# Tractive_System_Board_Rev8.net
KiCad netlist of a schematic drawn in EAGLE
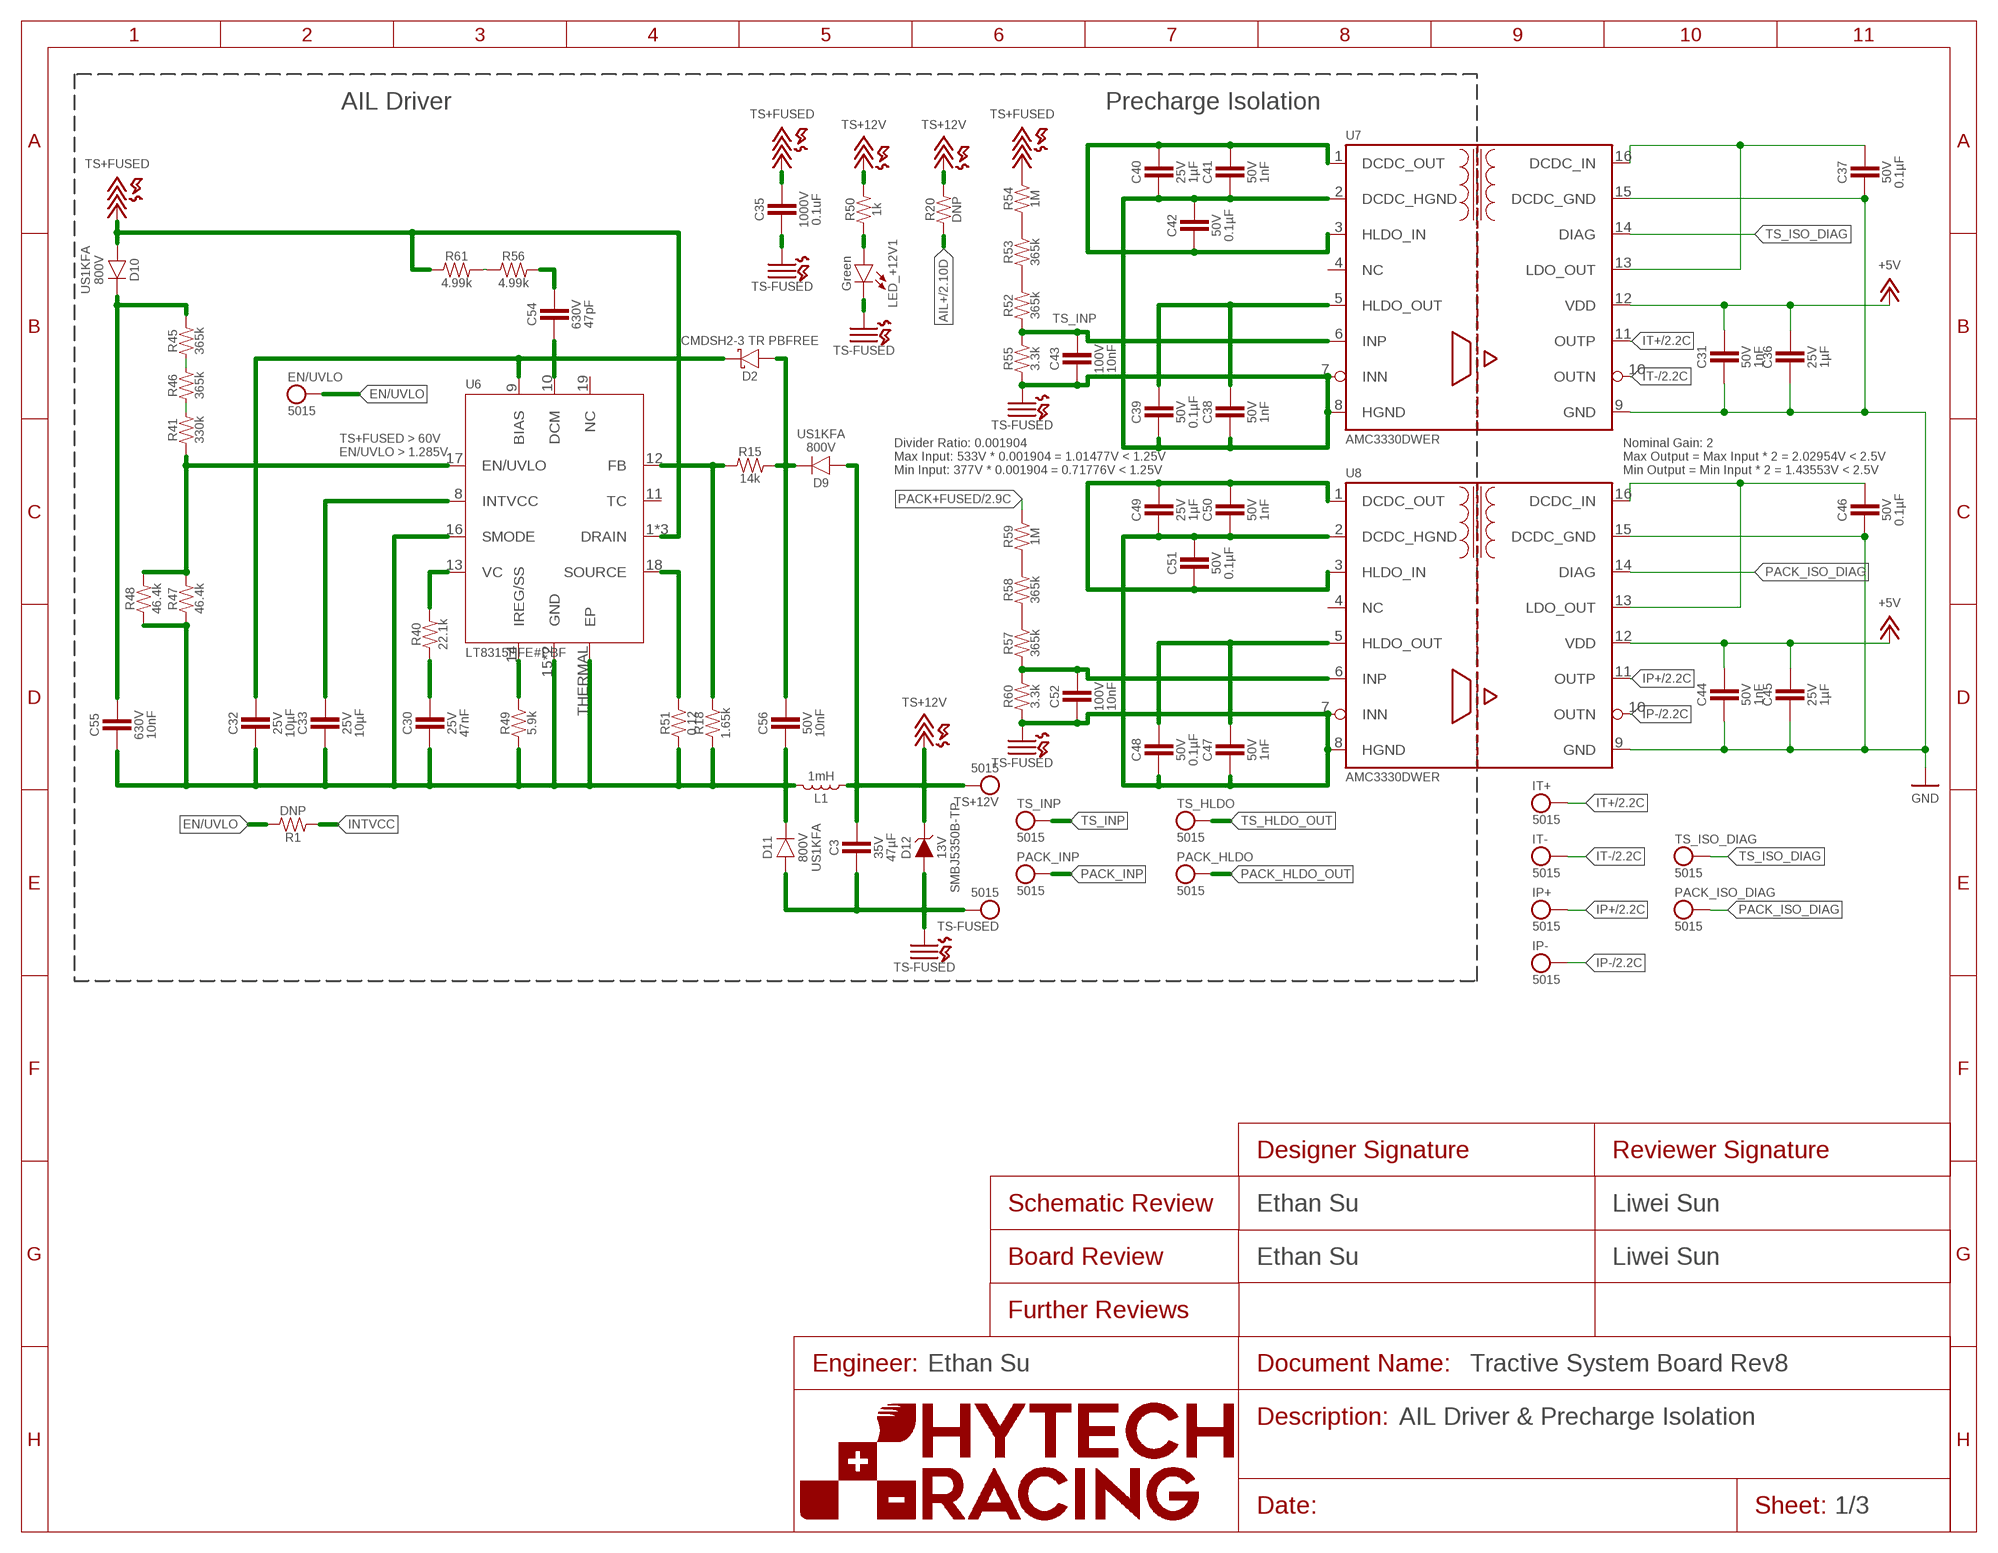
[diagram p0: schematic, sheet 1]
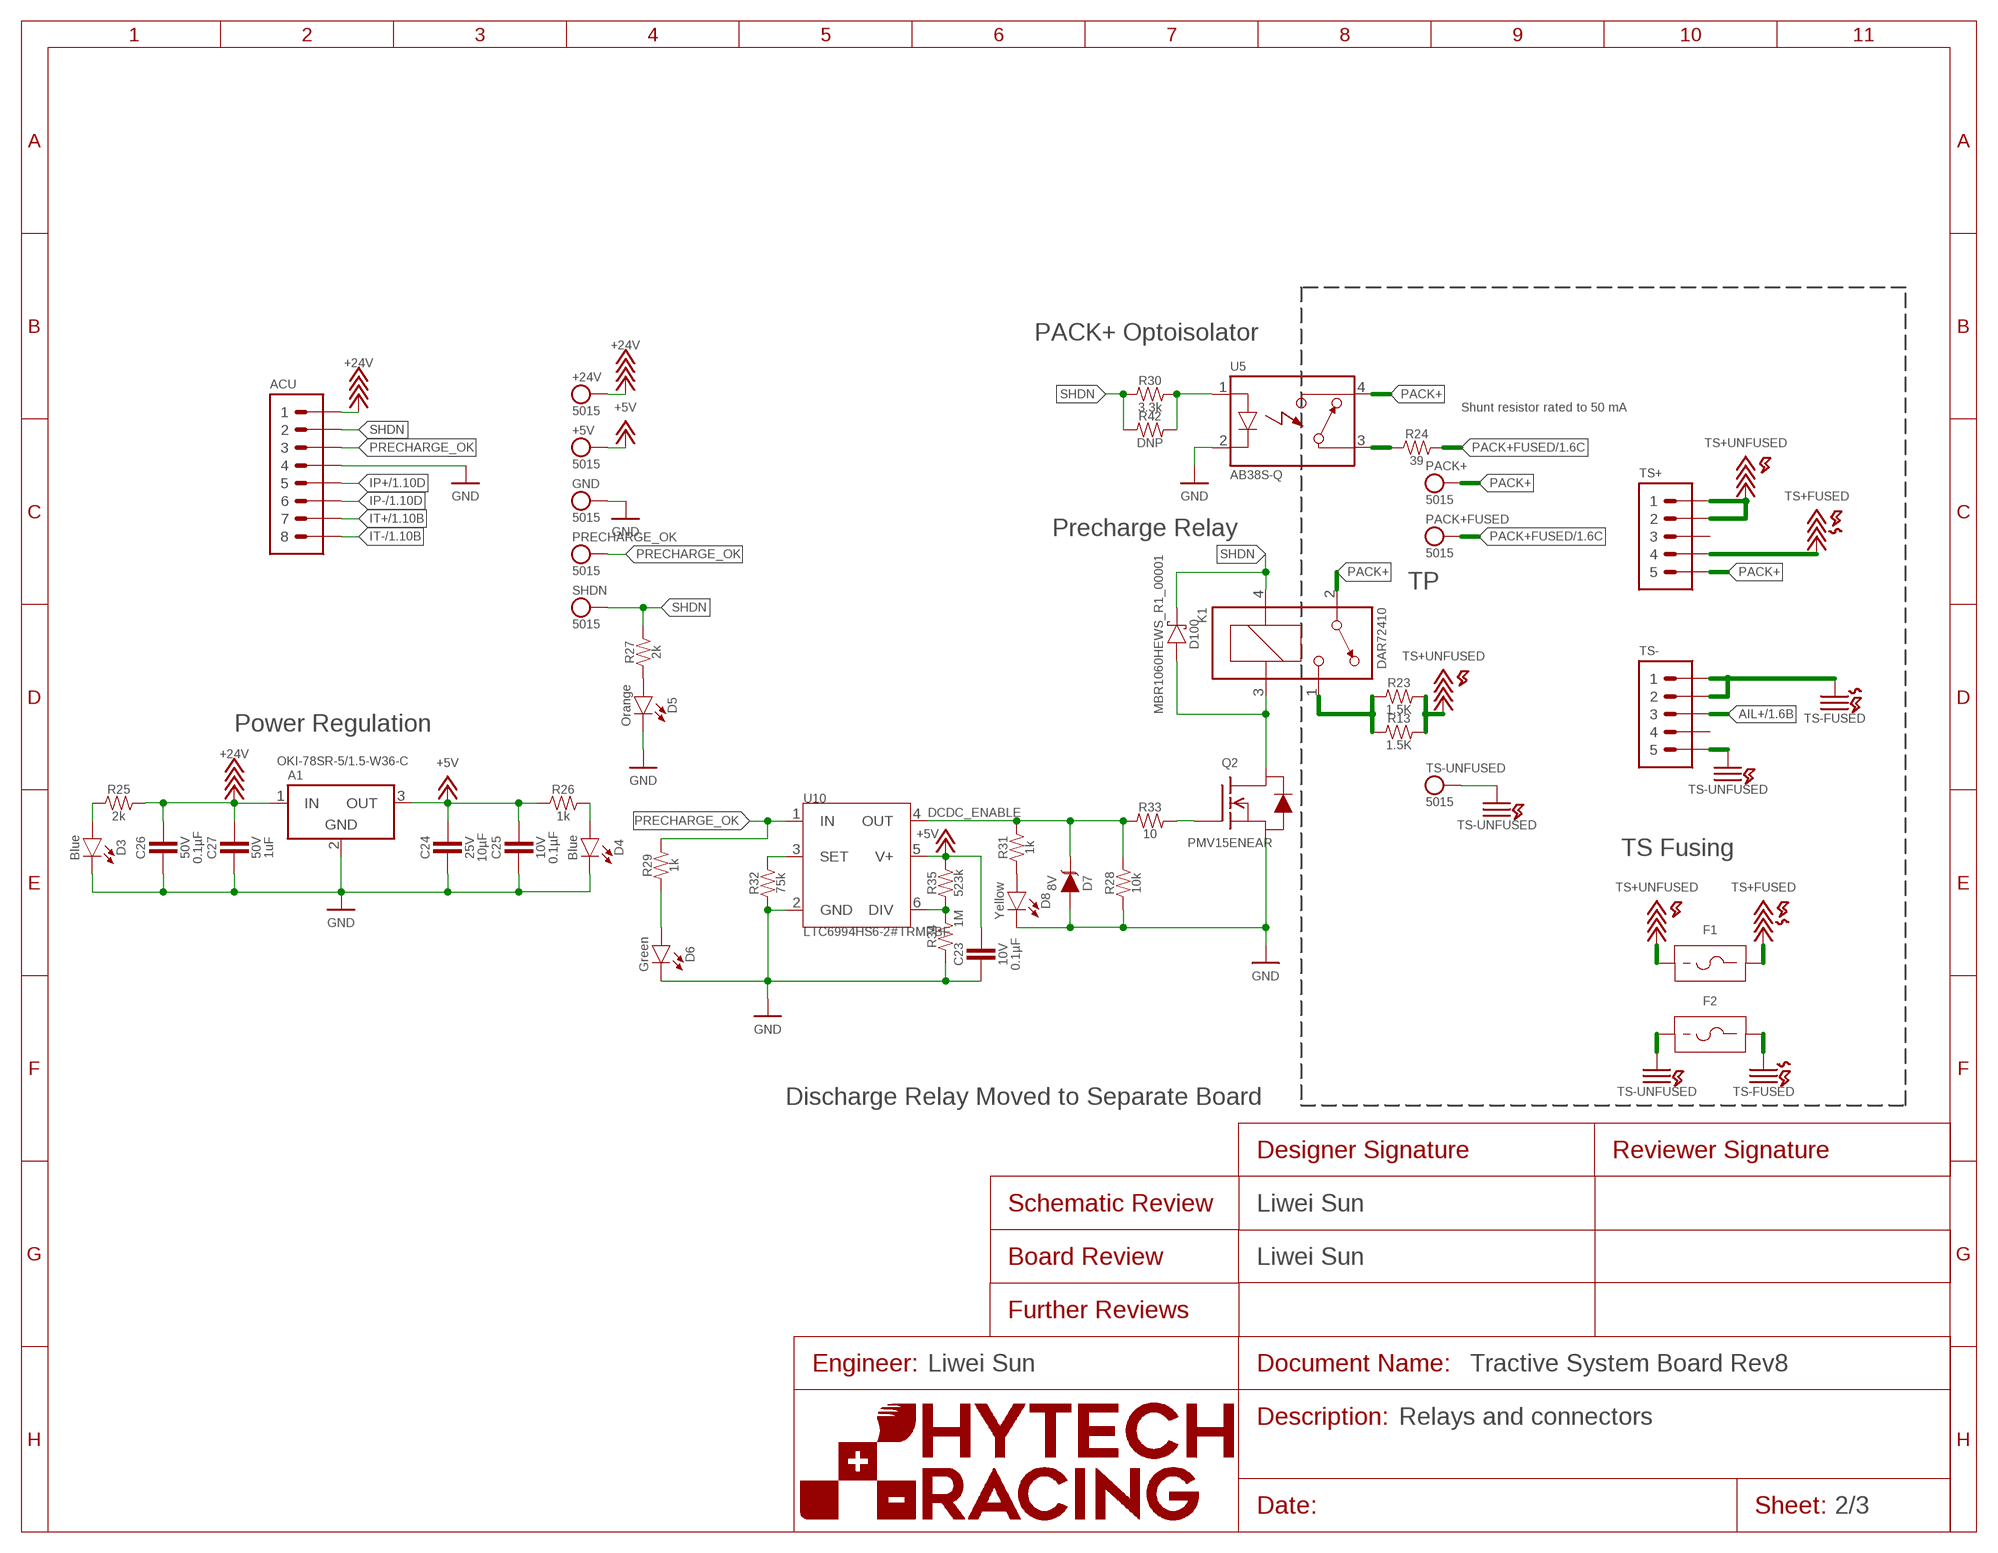
[diagram p1: schematic, sheet 2]
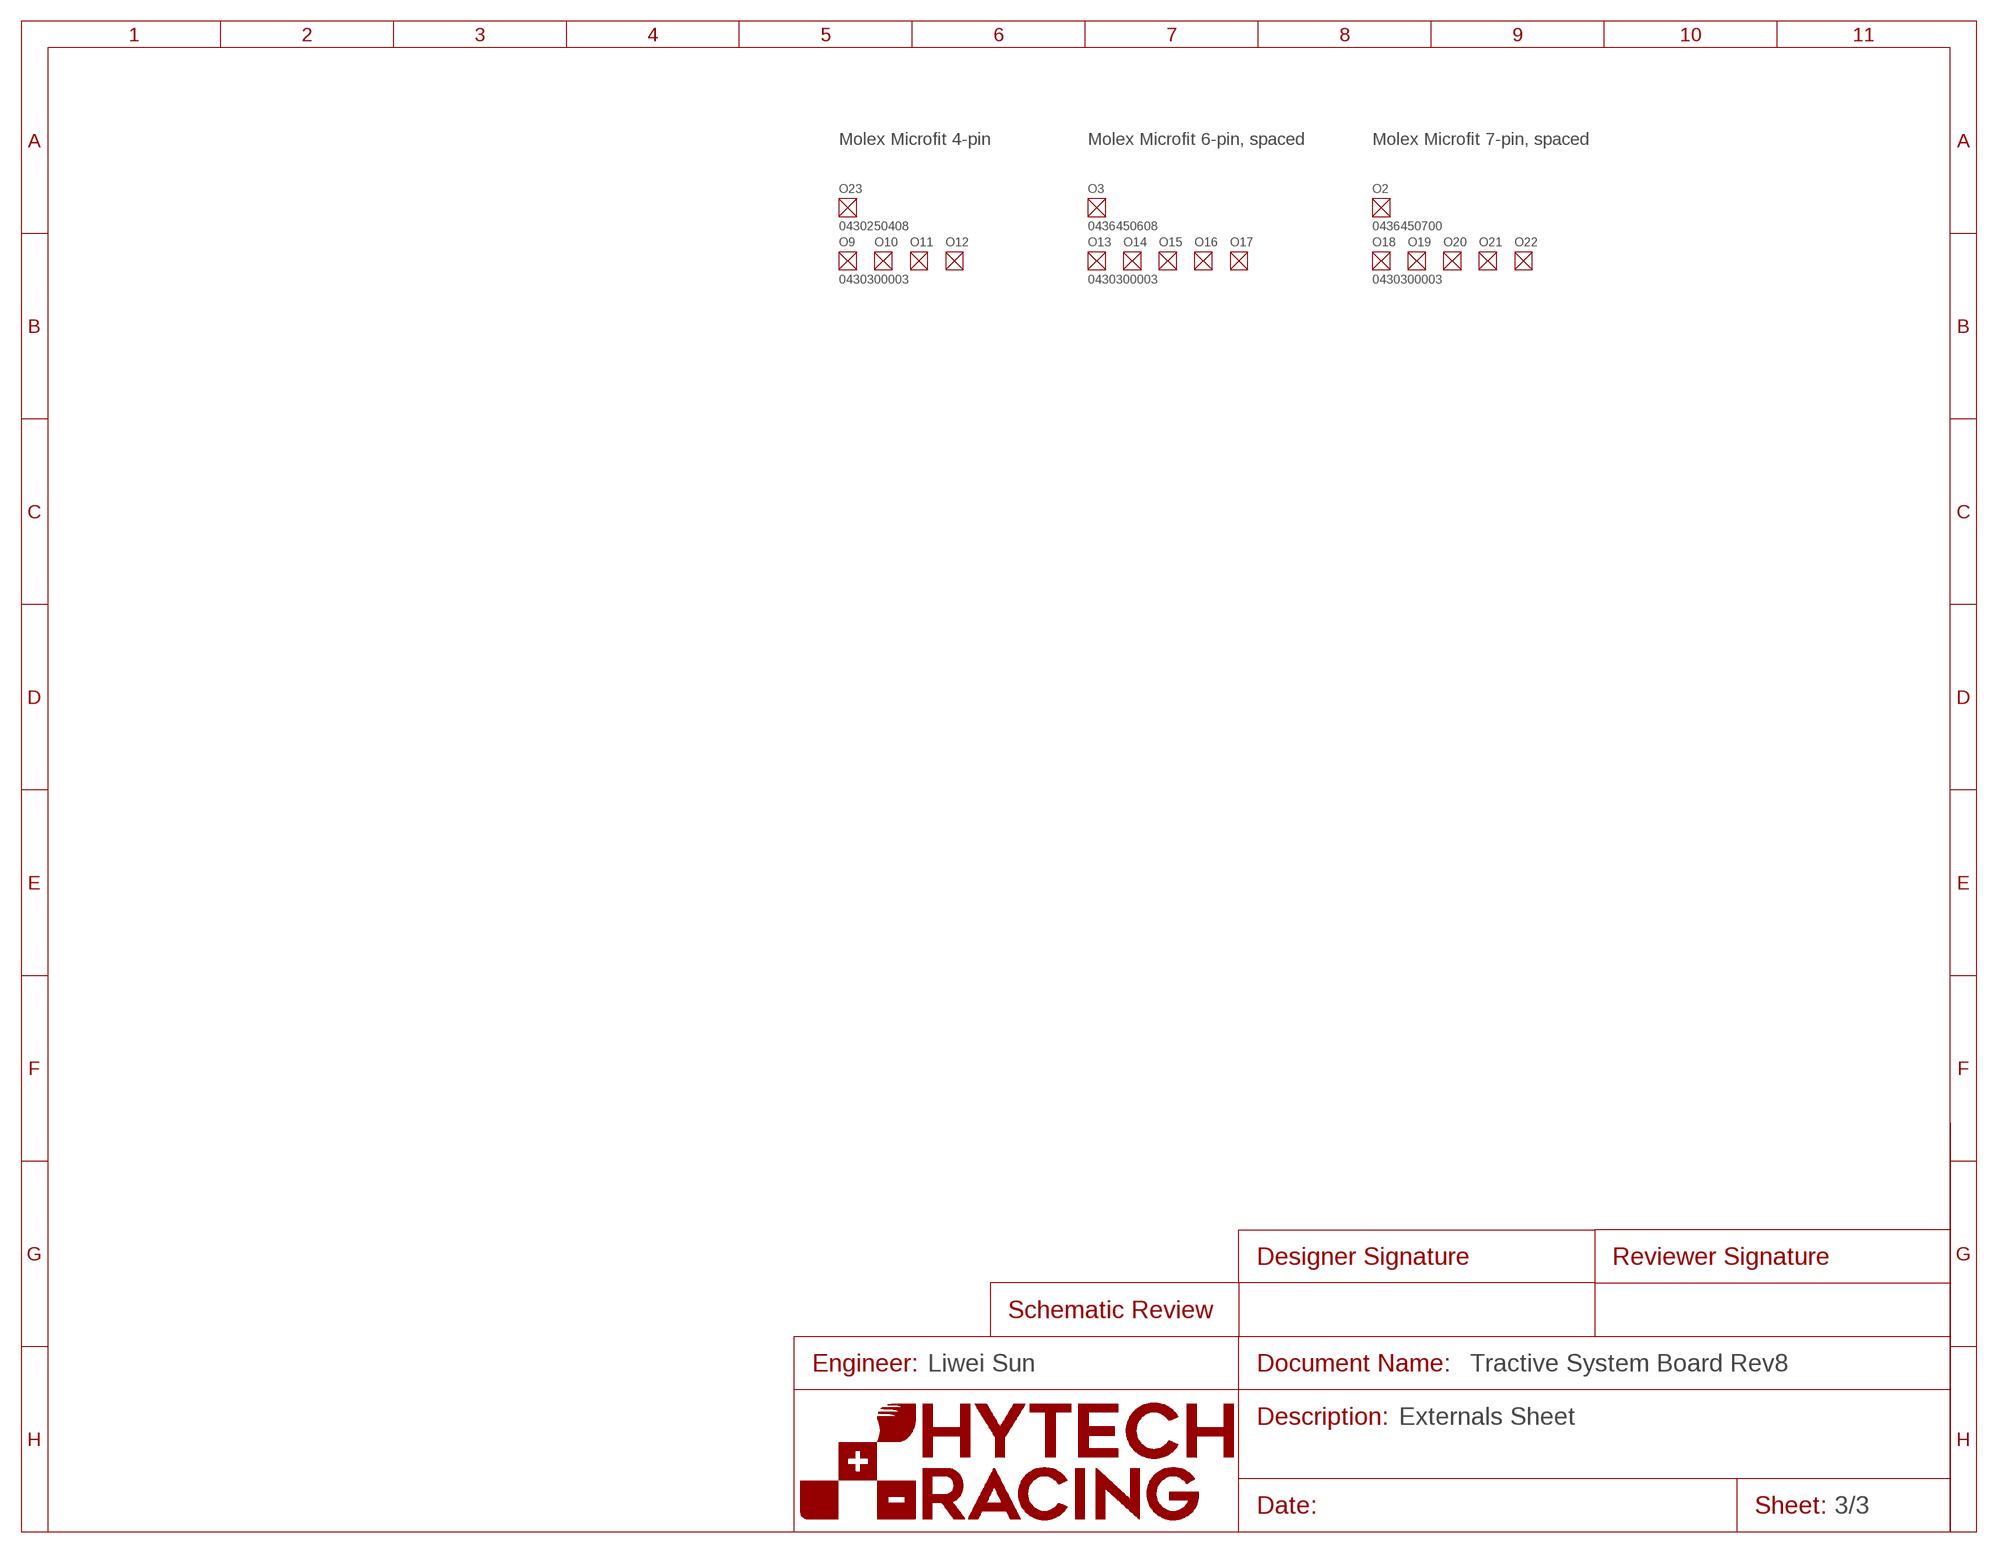
[diagram p2: schematic, sheet 3]

(export (version "E")
  (design (tool "Eeschema 10.0.6"))
  (components
    (comp (ref "C3")
      (value "CAPACITOR_2220_35V_47UF")
      (footprint "eagle-import:2220-CAP")
      (fields
        (field (name "CAPACITANCE") "47µF")
        (field (name "MANUFACTURER") "TDK Corporation")
        (field (name "MPN") "CGA9N1X7R1V476M230KC")
        (field (name "TOLERANCE") "20%")
        (field (name "VOLTAGE") "35V")
      )
      (libsource (lib "eagle-import") (part "CAPACITOR_?_222035V_47UF"))
    )
    (comp (ref "C30")
      (value "CAPACITOR_0603_25V_47NF")
      (footprint "eagle-import:0603-CAP")
      (fields
        (field (name "CAPACITANCE") "47nF")
        (field (name "MANUFACTURER") "Kyocera AVX")
        (field (name "MPN") "06033C473K4Z2A")
        (field (name "TOLERANCE") "10%")
        (field (name "VOLTAGE") "25V")
      )
      (libsource (lib "eagle-import") (part "CAPACITOR_?_060325V_47NF"))
    )
    (comp (ref "C31")
      (value "CAPACITOR_1206_50V_1NF")
      (footprint "eagle-import:1206-CAP")
      (fields
        (field (name "CAPACITANCE") "1nF")
        (field (name "MANUFACTURER") "KYOCERA AVX")
        (field (name "MPN") "KGM31BR71H102KT")
        (field (name "TOLERANCE") "10%")
        (field (name "VOLTAGE") "50V")
      )
      (libsource (lib "eagle-import") (part "CAPACITOR_?_120650V_1NF"))
    )
    (comp (ref "C32")
      (value "CAPACITOR_0603_25V_10UF")
      (footprint "eagle-import:0603-CAP")
      (fields
        (field (name "CAPACITANCE") "10µF")
        (field (name "MANUFACTURER") "Murata Electronics")
        (field (name "MPN") "GRM188R61E106MA73D")
        (field (name "TOLERANCE") "20%")
        (field (name "VOLTAGE") "25V")
      )
      (libsource (lib "eagle-import") (part "CAPACITOR_?_060325V_10UF"))
    )
    (comp (ref "C33")
      (value "CAPACITOR_0603_25V_10UF")
      (footprint "eagle-import:0603-CAP")
      (fields
        (field (name "CAPACITANCE") "10µF")
        (field (name "MANUFACTURER") "Murata Electronics")
        (field (name "MPN") "GRM188R61E106MA73D")
        (field (name "TOLERANCE") "20%")
        (field (name "VOLTAGE") "25V")
      )
      (libsource (lib "eagle-import") (part "CAPACITOR_?_060325V_10UF"))
    )
    (comp (ref "C35")
      (value "CAPACITOR_1812_1000V_0.1UF")
      (footprint "eagle-import:1812-CAP")
      (fields
        (field (name "CAPACITANCE") "0.1uF")
        (field (name "MANUFACTURER") "KEMET")
        (field (name "MPN") "C1812W104KDRAC7800")
        (field (name "TOLERANCE") "10%")
        (field (name "VOLTAGE") "1000V")
      )
      (libsource (lib "eagle-import") (part "CAPACITOR_?_18121000V_0.1UF"))
    )
    (comp (ref "C36")
      (value "CAPACITOR_1206_25V_1UF")
      (footprint "eagle-import:1206-CAP")
      (fields
        (field (name "CAPACITANCE") "1µF")
        (field (name "MANUFACTURER") "KYOCERA AVX")
        (field (name "MPN") "KGM31HR71E105KU")
        (field (name "TOLERANCE") "10%")
        (field (name "VOLTAGE") "25V")
      )
      (libsource (lib "eagle-import") (part "CAPACITOR_?_120625V_1UF"))
    )
    (comp (ref "C37")
      (value "CAPACITOR_0603_50V_0.1UF")
      (footprint "eagle-import:0603-CAP")
      (fields
        (field (name "CAPACITANCE") "0.1µF")
        (field (name "MANUFACTURER") "Yageo")
        (field (name "MPN") "CC0603KRX7R9BB104")
        (field (name "TOLERANCE") "10%")
        (field (name "VOLTAGE") "50V")
      )
      (libsource (lib "eagle-import") (part "CAPACITOR_?_060350V_0.1UF"))
    )
    (comp (ref "C38")
      (value "CAPACITOR_1206_50V_1NF")
      (footprint "eagle-import:1206-CAP")
      (fields
        (field (name "CAPACITANCE") "1nF")
        (field (name "MANUFACTURER") "KYOCERA AVX")
        (field (name "MPN") "KGM31BR71H102KT")
        (field (name "TOLERANCE") "10%")
        (field (name "VOLTAGE") "50V")
      )
      (libsource (lib "eagle-import") (part "CAPACITOR_?_120650V_1NF"))
    )
    (comp (ref "C39")
      (value "CAPACITOR_1206_50V_0.1UF")
      (footprint "eagle-import:1206-CAP")
      (fields
        (field (name "CAPACITANCE") "0.1µF")
        (field (name "MANUFACTURER") "TDK Corporation")
        (field (name "MPN") "C3216NP01H104J160AA")
        (field (name "TOLERANCE") "5%")
        (field (name "VOLTAGE") "50V")
      )
      (libsource (lib "eagle-import") (part "CAPACITOR_?_120650V_0.1UF"))
    )
    (comp (ref "C40")
      (value "CAPACITOR_0603_25V_1UF")
      (footprint "eagle-import:0603-CAP")
      (fields
        (field (name "CAPACITANCE") "1µF")
        (field (name "MANUFACTURER") "Samsung Electro-Mechanics")
        (field (name "MPN") "CL10B105KA8NNNC")
        (field (name "TOLERANCE") "10%")
        (field (name "VOLTAGE") "25V")
      )
      (libsource (lib "eagle-import") (part "CAPACITOR_?_060325V_1UF"))
    )
    (comp (ref "C41")
      (value "CAPACITOR_0603_50V_1NF")
      (footprint "eagle-import:0603-CAP")
      (fields
        (field (name "CAPACITANCE") "1nF")
        (field (name "MANUFACTURER") "KEMET")
        (field (name "MPN") "C0603C102K5RACTU")
        (field (name "TOLERANCE") "10%")
        (field (name "VOLTAGE") "50V")
      )
      (libsource (lib "eagle-import") (part "CAPACITOR_?_060350V_1NF"))
    )
    (comp (ref "C42")
      (value "CAPACITOR_0603_50V_0.1UF")
      (footprint "eagle-import:0603-CAP")
      (fields
        (field (name "CAPACITANCE") "0.1µF")
        (field (name "MANUFACTURER") "Yageo")
        (field (name "MPN") "CC0603KRX7R9BB104")
        (field (name "TOLERANCE") "10%")
        (field (name "VOLTAGE") "50V")
      )
      (libsource (lib "eagle-import") (part "CAPACITOR_?_060350V_0.1UF"))
    )
    (comp (ref "C43")
      (value "CAPACITOR_0603_100V_10NF")
      (footprint "eagle-import:0603-CAP")
      (fields
        (field (name "CAPACITANCE") "10nF")
        (field (name "MANUFACTURER") "Yageo")
        (field (name "MPN") "CC0603KRX7R0BB103")
        (field (name "TOLERANCE") "10%")
        (field (name "VOLTAGE") "100V")
      )
      (libsource (lib "eagle-import") (part "CAPACITOR_?_0603100V_10NF"))
    )
    (comp (ref "C44")
      (value "CAPACITOR_1206_50V_1NF")
      (footprint "eagle-import:1206-CAP")
      (fields
        (field (name "CAPACITANCE") "1nF")
        (field (name "MANUFACTURER") "KYOCERA AVX")
        (field (name "MPN") "KGM31BR71H102KT")
        (field (name "TOLERANCE") "10%")
        (field (name "VOLTAGE") "50V")
      )
      (libsource (lib "eagle-import") (part "CAPACITOR_?_120650V_1NF"))
    )
    (comp (ref "C45")
      (value "CAPACITOR_1206_25V_1UF")
      (footprint "eagle-import:1206-CAP")
      (fields
        (field (name "CAPACITANCE") "1µF")
        (field (name "MANUFACTURER") "KYOCERA AVX")
        (field (name "MPN") "KGM31HR71E105KU")
        (field (name "TOLERANCE") "10%")
        (field (name "VOLTAGE") "25V")
      )
      (libsource (lib "eagle-import") (part "CAPACITOR_?_120625V_1UF"))
    )
    (comp (ref "C46")
      (value "CAPACITOR_0603_50V_0.1UF")
      (footprint "eagle-import:0603-CAP")
      (fields
        (field (name "CAPACITANCE") "0.1µF")
        (field (name "MANUFACTURER") "Yageo")
        (field (name "MPN") "CC0603KRX7R9BB104")
        (field (name "TOLERANCE") "10%")
        (field (name "VOLTAGE") "50V")
      )
      (libsource (lib "eagle-import") (part "CAPACITOR_?_060350V_0.1UF"))
    )
    (comp (ref "C47")
      (value "CAPACITOR_1206_50V_1NF")
      (footprint "eagle-import:1206-CAP")
      (fields
        (field (name "CAPACITANCE") "1nF")
        (field (name "MANUFACTURER") "KYOCERA AVX")
        (field (name "MPN") "KGM31BR71H102KT")
        (field (name "TOLERANCE") "10%")
        (field (name "VOLTAGE") "50V")
      )
      (libsource (lib "eagle-import") (part "CAPACITOR_?_120650V_1NF"))
    )
    (comp (ref "C48")
      (value "CAPACITOR_1206_50V_0.1UF")
      (footprint "eagle-import:1206-CAP")
      (fields
        (field (name "CAPACITANCE") "0.1µF")
        (field (name "MANUFACTURER") "TDK Corporation")
        (field (name "MPN") "C3216NP01H104J160AA")
        (field (name "TOLERANCE") "5%")
        (field (name "VOLTAGE") "50V")
      )
      (libsource (lib "eagle-import") (part "CAPACITOR_?_120650V_0.1UF"))
    )
    (comp (ref "C49")
      (value "CAPACITOR_0603_25V_1UF")
      (footprint "eagle-import:0603-CAP")
      (fields
        (field (name "CAPACITANCE") "1µF")
        (field (name "MANUFACTURER") "Samsung Electro-Mechanics")
        (field (name "MPN") "CL10B105KA8NNNC")
        (field (name "TOLERANCE") "10%")
        (field (name "VOLTAGE") "25V")
      )
      (libsource (lib "eagle-import") (part "CAPACITOR_?_060325V_1UF"))
    )
    (comp (ref "C50")
      (value "CAPACITOR_0603_50V_1NF")
      (footprint "eagle-import:0603-CAP")
      (fields
        (field (name "CAPACITANCE") "1nF")
        (field (name "MANUFACTURER") "KEMET")
        (field (name "MPN") "C0603C102K5RACTU")
        (field (name "TOLERANCE") "10%")
        (field (name "VOLTAGE") "50V")
      )
      (libsource (lib "eagle-import") (part "CAPACITOR_?_060350V_1NF"))
    )
    (comp (ref "C51")
      (value "CAPACITOR_0603_50V_0.1UF")
      (footprint "eagle-import:0603-CAP")
      (fields
        (field (name "CAPACITANCE") "0.1µF")
        (field (name "MANUFACTURER") "Yageo")
        (field (name "MPN") "CC0603KRX7R9BB104")
        (field (name "TOLERANCE") "10%")
        (field (name "VOLTAGE") "50V")
      )
      (libsource (lib "eagle-import") (part "CAPACITOR_?_060350V_0.1UF"))
    )
    (comp (ref "C52")
      (value "CAPACITOR_0603_100V_10NF")
      (footprint "eagle-import:0603-CAP")
      (fields
        (field (name "CAPACITANCE") "10nF")
        (field (name "MANUFACTURER") "Yageo")
        (field (name "MPN") "CC0603KRX7R0BB103")
        (field (name "TOLERANCE") "10%")
        (field (name "VOLTAGE") "100V")
      )
      (libsource (lib "eagle-import") (part "CAPACITOR_?_0603100V_10NF"))
    )
    (comp (ref "C54")
      (value "CAPACITOR_1206_630V_47PF")
      (footprint "eagle-import:1206-CAP")
      (fields
        (field (name "CAPACITANCE") "47pF")
        (field (name "MANUFACTURER") "Murata Electronics")
        (field (name "MPN") "GCM31A7U2J470JX01D")
        (field (name "TOLERANCE") "5%")
        (field (name "VOLTAGE") "630V")
      )
      (libsource (lib "eagle-import") (part "CAPACITOR_?_1206630V_47PF"))
    )
    (comp (ref "C55")
      (value "CAPACITOR_1206_630V_10NF")
      (footprint "eagle-import:1206-CAP")
      (fields
        (field (name "CAPACITANCE") "10nF")
        (field (name "MANUFACTURER") "TDK Corporation")
        (field (name "MPN") "CGA5L4C0G2J103J160AA")
        (field (name "TOLERANCE") "5%")
        (field (name "VOLTAGE") "630V")
      )
      (libsource (lib "eagle-import") (part "CAPACITOR_?_1206630V_10NF"))
    )
    (comp (ref "C56")
      (value "CAPACITOR_0603_50V_10NF")
      (footprint "eagle-import:0603-CAP")
      (fields
        (field (name "CAPACITANCE") "10nF")
        (field (name "MANUFACTURER") "TDK Corporation")
        (field (name "MPN") "C1608C0G1H103J080AA")
        (field (name "TOLERANCE") "5%")
        (field (name "VOLTAGE") "50V")
      )
      (libsource (lib "eagle-import") (part "CAPACITOR_?_060350V_10NF"))
    )
    (comp (ref "D2")
      (value "SCHOTTKY_SOD323_30VV")
      (footprint "eagle-import:SOD-323")
      (fields
        (field (name "MANUFACTURER") "Central Semiconductor Corp")
        (field (name "MPN") "CMDSH2-3 TR PBFREE")
        (field (name "VOLTAGE") "30V")
      )
      (libsource (lib "eagle-import") (part "SCHOTTKY_?_SOD32330VV"))
    )
    (comp (ref "D9")
      (value "RECTIFIER_800V_SOD-123FA")
      (footprint "eagle-import:SOD-123FA")
      (fields
        (field (name "MANUFACTURER") "onsemi")
        (field (name "MPN") "US1KFA")
        (field (name "VOLTAGE") "800V")
      )
      (libsource (lib "eagle-import") (part "RECTIFIER__?SOD-123FA800V"))
    )
    (comp (ref "D10")
      (value "RECTIFIER_800V_SOD-123FA")
      (footprint "eagle-import:SOD-123FA")
      (fields
        (field (name "MANUFACTURER") "onsemi")
        (field (name "MPN") "US1KFA")
        (field (name "VOLTAGE") "800V")
      )
      (libsource (lib "eagle-import") (part "RECTIFIER__?SOD-123FA800V"))
    )
    (comp (ref "D11")
      (value "RECTIFIER_800V_SOD-123FA")
      (footprint "eagle-import:SOD-123FA")
      (fields
        (field (name "MANUFACTURER") "onsemi")
        (field (name "MPN") "US1KFA")
        (field (name "VOLTAGE") "800V")
      )
      (libsource (lib "eagle-import") (part "RECTIFIER__?SOD-123FA800V"))
    )
    (comp (ref "D12")
      (value "ZENER_SMB(DO-214AA)_13V")
      (footprint "eagle-import:SMB(DO-214AA)")
      (fields
        (field (name "MANUFACTURER") "Micro Commercial Co")
        (field (name "MPN") "SMBJ5350B-TP")
        (field (name "VOLTAGE") "13V")
      )
      (libsource (lib "eagle-import") (part "ZENER_?_SMB(DO-214AA)13V"))
    )
    (comp (ref "EN/UVLO")
      (value "TEST_POINT")
      (footprint "eagle-import:5015")
      (fields (field (name "MPN") "5015") (field (name "MANUFACTURER") "Keystone Electronics"))
      (libsource (lib "eagle-import") (part "TEST_POINT"))
    )
    (comp (ref "IP+")
      (value "TEST_POINT")
      (footprint "eagle-import:5015")
      (fields (field (name "MPN") "5015") (field (name "MANUFACTURER") "Keystone Electronics"))
      (libsource (lib "eagle-import") (part "TEST_POINT"))
    )
    (comp (ref "IP-")
      (value "TEST_POINT")
      (footprint "eagle-import:5015")
      (fields (field (name "MPN") "5015") (field (name "MANUFACTURER") "Keystone Electronics"))
      (libsource (lib "eagle-import") (part "TEST_POINT"))
    )
    (comp (ref "IT+")
      (value "TEST_POINT")
      (footprint "eagle-import:5015")
      (fields (field (name "MPN") "5015") (field (name "MANUFACTURER") "Keystone Electronics"))
      (libsource (lib "eagle-import") (part "TEST_POINT"))
    )
    (comp (ref "IT-")
      (value "TEST_POINT")
      (footprint "eagle-import:5015")
      (fields (field (name "MPN") "5015") (field (name "MANUFACTURER") "Keystone Electronics"))
      (libsource (lib "eagle-import") (part "TEST_POINT"))
    )
    (comp (ref "L1")
      (value "INDUCTOR_SRR0745A_1MH")
      (footprint "eagle-import:SRR0745A-102M")
      (fields
        (field (name "INDUCTANCE") "1mH")
        (field (name "MANUFACTURER") "Bourns Inc.")
        (field (name "MPN") "SRR0745A-102M")
        (field (name "TOLERANCE") "20%")
      )
      (libsource (lib "eagle-import") (part "INDUCTOR_?_SRR0745A1MH"))
    )
    (comp (ref "LED_+12V1")
      (value "LED_0603_GREEN")
      (footprint "eagle-import:0603-LED")
      (fields
        (field (name "COLOR") "Green")
        (field (name "MANUFACTURER") "Kingbright")
        (field (name "MPN") "APT1608ZGCK")
      )
      (libsource (lib "eagle-import") (part "LED_?_0603GREEN"))
    )
    (comp (ref "PACK_HLDO")
      (value "TEST_POINT")
      (footprint "eagle-import:5015")
      (fields (field (name "MPN") "5015") (field (name "MANUFACTURER") "Keystone Electronics"))
      (libsource (lib "eagle-import") (part "TEST_POINT"))
    )
    (comp (ref "PACK_INP")
      (value "TEST_POINT")
      (footprint "eagle-import:5015")
      (fields (field (name "MPN") "5015") (field (name "MANUFACTURER") "Keystone Electronics"))
      (libsource (lib "eagle-import") (part "TEST_POINT"))
    )
    (comp (ref "PACK_ISO_DIAG")
      (value "TEST_POINT")
      (footprint "eagle-import:5015")
      (fields (field (name "MPN") "5015") (field (name "MANUFACTURER") "Keystone Electronics"))
      (libsource (lib "eagle-import") (part "TEST_POINT"))
    )
    (comp (ref "R1")
      (value "RESISTOR_0603_DNP")
      (footprint "eagle-import:0603-RES")
      (fields (field (name "RESISTANCE") "DNP"))
      (libsource (lib "eagle-import") (part "RESISTOR_?_0603DNP"))
    )
    (comp (ref "R15")
      (value "RESISTOR_0603_14K")
      (footprint "eagle-import:0603-RES")
      (fields
        (field (name "MANUFACTURER") "YAGEO")
        (field (name "MPN") "RT0603BRB0714KL")
        (field (name "POWER") "0.1W")
        (field (name "RESISTANCE") "14k")
      )
      (libsource (lib "eagle-import") (part "RESISTOR_?_060314K"))
    )
    (comp (ref "R18")
      (value "RESISTOR_0603_1.65K")
      (footprint "eagle-import:0603-RES")
      (fields
        (field (name "MANUFACTURER") "Yageo")
        (field (name "MPN") "RC0603FR-071K65L")
        (field (name "POWER") "0.1W")
        (field (name "RESISTANCE") "1.65k")
      )
      (libsource (lib "eagle-import") (part "RESISTOR_?_06031.65K"))
    )
    (comp (ref "R20")
      (value "RESISTOR_0603_DNP")
      (footprint "eagle-import:0603-RES")
      (fields (field (name "RESISTANCE") "DNP"))
      (libsource (lib "eagle-import") (part "RESISTOR_?_0603DNP"))
    )
    (comp (ref "R40")
      (value "RESISTOR_0603_22.1K")
      (footprint "eagle-import:0603-RES")
      (fields
        (field (name "MANUFACTURER") "Panasonic Electronic Components")
        (field (name "MPN") "ERA-3AEB2212V")
        (field (name "POWER") "0.1W")
        (field (name "RESISTANCE") "22.1k")
      )
      (libsource (lib "eagle-import") (part "RESISTOR_?_060322.1K"))
    )
    (comp (ref "R41")
      (value "RESISTOR_0805_HV330K")
      (footprint "eagle-import:0805-RES")
      (fields
        (field (name "MANUFACTURER") "Rohm Semiconductor")
        (field (name "MPN") "KTR10EZPF3303")
        (field (name "POWER") "0.125W")
        (field (name "RESISTANCE") "330k")
      )
      (libsource (lib "eagle-import") (part "RESISTOR_?_0805HV330K"))
    )
    (comp (ref "R45")
      (value "RESISTOR_0805_HV365K")
      (footprint "eagle-import:0805-RES")
      (fields
        (field (name "MANUFACTURER") "Rohm")
        (field (name "MPN") "KTR10EZPF3653")
        (field (name "POWER") "0.125W")
        (field (name "RESISTANCE") "365k")
      )
      (libsource (lib "eagle-import") (part "RESISTOR_?_0805HV365K"))
    )
    (comp (ref "R46")
      (value "RESISTOR_0805_HV365K")
      (footprint "eagle-import:0805-RES")
      (fields
        (field (name "MANUFACTURER") "Rohm")
        (field (name "MPN") "KTR10EZPF3653")
        (field (name "POWER") "0.125W")
        (field (name "RESISTANCE") "365k")
      )
      (libsource (lib "eagle-import") (part "RESISTOR_?_0805HV365K"))
    )
    (comp (ref "R47")
      (value "RESISTOR_1206_HV46.4K")
      (footprint "eagle-import:1206-RES")
      (fields
        (field (name "MANUFACTURER") "Rohm Semiconductor")
        (field (name "MPN") "KTR18EZPF4642")
        (field (name "POWER") "0.25W")
        (field (name "RESISTANCE") "46.4k")
      )
      (libsource (lib "eagle-import") (part "RESISTOR_?_1206HV46.4K"))
    )
    (comp (ref "R48")
      (value "RESISTOR_1206_HV46.4K")
      (footprint "eagle-import:1206-RES")
      (fields
        (field (name "MANUFACTURER") "Rohm Semiconductor")
        (field (name "MPN") "KTR18EZPF4642")
        (field (name "POWER") "0.25W")
        (field (name "RESISTANCE") "46.4k")
      )
      (libsource (lib "eagle-import") (part "RESISTOR_?_1206HV46.4K"))
    )
    (comp (ref "R49")
      (value "RESISTOR_0603_5.9K")
      (footprint "eagle-import:0603-RES")
      (fields
        (field (name "MANUFACTURER") "Panasonic Electronic Components")
        (field (name "MPN") "ERA-3AEB5901V")
        (field (name "POWER") "0.1W")
        (field (name "RESISTANCE") "5.9k")
      )
      (libsource (lib "eagle-import") (part "RESISTOR_?_06035.9K"))
    )
    (comp (ref "R50")
      (value "RESISTOR_0603_1K")
      (footprint "eagle-import:0603-RES")
      (fields
        (field (name "MANUFACTURER") "TE Connectivity Passive Product")
        (field (name "MPN") " CPF-A-0603B1K0E")
        (field (name "POWER") "0.0625W")
        (field (name "RESISTANCE") "1k")
      )
      (libsource (lib "eagle-import") (part "RESISTOR_?_06031K"))
    )
    (comp (ref "R51")
      (value "RESISTOR_0603_0.12")
      (footprint "eagle-import:0603-RES")
      (fields
        (field (name "MANUFACTURER") "Rohm Semiconductor")
        (field (name "MPN") "UCR03EVPFLR120")
        (field (name "POWER") "0.25W")
        (field (name "RESISTANCE") "0.12")
      )
      (libsource (lib "eagle-import") (part "RESISTOR_?_06030.12"))
    )
    (comp (ref "R52")
      (value "RESISTOR_0805_HV365K")
      (footprint "eagle-import:0805-RES")
      (fields
        (field (name "MANUFACTURER") "Rohm")
        (field (name "MPN") "KTR10EZPF3653")
        (field (name "POWER") "0.125W")
        (field (name "RESISTANCE") "365k")
      )
      (libsource (lib "eagle-import") (part "RESISTOR_?_0805HV365K"))
    )
    (comp (ref "R53")
      (value "RESISTOR_0805_HV365K")
      (footprint "eagle-import:0805-RES")
      (fields
        (field (name "MANUFACTURER") "Rohm")
        (field (name "MPN") "KTR10EZPF3653")
        (field (name "POWER") "0.125W")
        (field (name "RESISTANCE") "365k")
      )
      (libsource (lib "eagle-import") (part "RESISTOR_?_0805HV365K"))
    )
    (comp (ref "R54")
      (value "RESISTOR_0805_HV1M")
      (footprint "eagle-import:0805-RES")
      (fields
        (field (name "MANUFACTURER") "Rohm Semiconductor")
        (field (name "MPN") "KTR10EZPF1004")
        (field (name "POWER") "0.125W")
        (field (name "RESISTANCE") "1M")
      )
      (libsource (lib "eagle-import") (part "RESISTOR_?_0805HV1M"))
    )
    (comp (ref "R55")
      (value "RESISTOR_0603_HV3.3K")
      (footprint "eagle-import:0603-RES")
      (fields
        (field (name "MANUFACTURER") "Rohm")
        (field (name "MPN") "KTR03EZPF3301")
        (field (name "POWER") "0.1W")
        (field (name "RESISTANCE") "3.3k")
      )
      (libsource (lib "eagle-import") (part "RESISTOR_?_0603HV3.3K"))
    )
    (comp (ref "R56")
      (value "RESISTOR_1206_HV4.99K")
      (footprint "eagle-import:1206-RES")
      (fields
        (field (name "MANUFACTURER") "Rohm Semiconductor")
        (field (name "MPN") "KTR18EZPF4991")
        (field (name "POWER") "0.25W")
        (field (name "RESISTANCE") "4.99k")
      )
      (libsource (lib "eagle-import") (part "RESISTOR_?_1206HV4.99K"))
    )
    (comp (ref "R57")
      (value "RESISTOR_0805_HV365K")
      (footprint "eagle-import:0805-RES")
      (fields
        (field (name "MANUFACTURER") "Rohm")
        (field (name "MPN") "KTR10EZPF3653")
        (field (name "POWER") "0.125W")
        (field (name "RESISTANCE") "365k")
      )
      (libsource (lib "eagle-import") (part "RESISTOR_?_0805HV365K"))
    )
    (comp (ref "R58")
      (value "RESISTOR_0805_HV365K")
      (footprint "eagle-import:0805-RES")
      (fields
        (field (name "MANUFACTURER") "Rohm")
        (field (name "MPN") "KTR10EZPF3653")
        (field (name "POWER") "0.125W")
        (field (name "RESISTANCE") "365k")
      )
      (libsource (lib "eagle-import") (part "RESISTOR_?_0805HV365K"))
    )
    (comp (ref "R59")
      (value "RESISTOR_0805_HV1M")
      (footprint "eagle-import:0805-RES")
      (fields
        (field (name "MANUFACTURER") "Rohm Semiconductor")
        (field (name "MPN") "KTR10EZPF1004")
        (field (name "POWER") "0.125W")
        (field (name "RESISTANCE") "1M")
      )
      (libsource (lib "eagle-import") (part "RESISTOR_?_0805HV1M"))
    )
    (comp (ref "R60")
      (value "RESISTOR_0603_HV3.3K")
      (footprint "eagle-import:0603-RES")
      (fields
        (field (name "MANUFACTURER") "Rohm")
        (field (name "MPN") "KTR03EZPF3301")
        (field (name "POWER") "0.1W")
        (field (name "RESISTANCE") "3.3k")
      )
      (libsource (lib "eagle-import") (part "RESISTOR_?_0603HV3.3K"))
    )
    (comp (ref "R61")
      (value "RESISTOR_1206_HV4.99K")
      (footprint "eagle-import:1206-RES")
      (fields
        (field (name "MANUFACTURER") "Rohm Semiconductor")
        (field (name "MPN") "KTR18EZPF4991")
        (field (name "POWER") "0.25W")
        (field (name "RESISTANCE") "4.99k")
      )
      (libsource (lib "eagle-import") (part "RESISTOR_?_1206HV4.99K"))
    )
    (comp (ref "TS+12V")
      (value "TEST_POINT")
      (footprint "eagle-import:5015")
      (fields (field (name "MPN") "5015") (field (name "MANUFACTURER") "Keystone Electronics"))
      (libsource (lib "eagle-import") (part "TEST_POINT"))
    )
    (comp (ref "TS-FUSED")
      (value "TEST_POINT")
      (footprint "eagle-import:5015")
      (fields (field (name "MPN") "5015") (field (name "MANUFACTURER") "Keystone Electronics"))
      (libsource (lib "eagle-import") (part "TEST_POINT"))
    )
    (comp (ref "TS_HLDO")
      (value "TEST_POINT")
      (footprint "eagle-import:5015")
      (fields (field (name "MPN") "5015") (field (name "MANUFACTURER") "Keystone Electronics"))
      (libsource (lib "eagle-import") (part "TEST_POINT"))
    )
    (comp (ref "TS_INP")
      (value "TEST_POINT")
      (footprint "eagle-import:5015")
      (fields (field (name "MPN") "5015") (field (name "MANUFACTURER") "Keystone Electronics"))
      (libsource (lib "eagle-import") (part "TEST_POINT"))
    )
    (comp (ref "TS_ISO_DIAG")
      (value "TEST_POINT")
      (footprint "eagle-import:5015")
      (fields (field (name "MPN") "5015") (field (name "MANUFACTURER") "Keystone Electronics"))
      (libsource (lib "eagle-import") (part "TEST_POINT"))
    )
    (comp (ref "U6")
      (value "LT8315")
      (footprint "eagle-import:TSSOP-20(16)")
      (fields (field (name "MPN") "LT8315HFE#PBF") (field (name "MANUFACTURER") "Analog Devices Inc."))
      (libsource (lib "eagle-import") (part "LT8315"))
    )
    (comp (ref "U7")
      (value "AMC3330_AIRGAP")
      (footprint "eagle-import:SOIC-16W-AIRGAP")
      (fields (field (name "MPN") "AMC3330DWER") (field (name "MANUFACTURER") "Texas Instruments"))
      (libsource (lib "eagle-import") (part "AMC3330_AIRGAP"))
    )
    (comp (ref "U8")
      (value "AMC3330_AIRGAP")
      (footprint "eagle-import:SOIC-16W-AIRGAP")
      (fields (field (name "MPN") "AMC3330DWER") (field (name "MANUFACTURER") "Texas Instruments"))
      (libsource (lib "eagle-import") (part "AMC3330_AIRGAP"))
    )
    (comp (ref "+5V")
      (value "TEST_POINT")
      (footprint "eagle-import:5015")
      (fields (field (name "MPN") "5015") (field (name "MANUFACTURER") "Keystone Electronics"))
      (libsource (lib "eagle-import") (part "TEST_POINT"))
    )
    (comp (ref "+24V")
      (value "TEST_POINT")
      (footprint "eagle-import:5015")
      (fields (field (name "MPN") "5015") (field (name "MANUFACTURER") "Keystone Electronics"))
      (libsource (lib "eagle-import") (part "TEST_POINT"))
    )
    (comp (ref "A1")
      (value "VOLTAGE_REGULATOR_MODULE_OKI-78SR_5V")
      (footprint "eagle-import:OKI-78SR")
      (fields
        (field (name "MANUFACTURER") "Murata Power Solutions Inc.")
        (field (name "MPN") "OKI-78SR-5/1.5-W36-C")
      )
      (libsource (lib "eagle-import") (part "VOLTAGE_REGULATOR_MODULE_?_OKI-78SR5V"))
    )
    (comp (ref "ACU")
      (value "CONNECTOR-8_μF_T_V_BLACK")
      (footprint "eagle-import:MOLEX_MICROFIT_PTH_VERTICAL_08_DUAL")
      (fields (field (name "MANUFACTURER") "Molex") (field (name "MPN") "430450814"))
      (libsource (lib "eagle-import") (part "CONNECTOR-8_?_μF_T_VBLACK"))
    )
    (comp (ref "C23")
      (value "CAPACITOR_0603_10V_0.1UF")
      (footprint "eagle-import:0603-CAP")
      (fields
        (field (name "CAPACITANCE") "0.1µF")
        (field (name "MANUFACTURER") "Vishay Vitramon")
        (field (name "MPN") "VJ0603Y104JXQPW1BC")
        (field (name "TOLERANCE") "5%")
        (field (name "VOLTAGE") "10V")
      )
      (libsource (lib "eagle-import") (part "CAPACITOR_?_060310V_0.1UF"))
    )
    (comp (ref "C24")
      (value "CAPACITOR_0603_25V_10UF")
      (footprint "eagle-import:0603-CAP")
      (fields
        (field (name "CAPACITANCE") "10µF")
        (field (name "MANUFACTURER") "Murata Electronics")
        (field (name "MPN") "GRM188R61E106MA73D")
        (field (name "TOLERANCE") "20%")
        (field (name "VOLTAGE") "25V")
      )
      (libsource (lib "eagle-import") (part "CAPACITOR_?_060325V_10UF"))
    )
    (comp (ref "C25")
      (value "CAPACITOR_0603_10V_0.1UF")
      (footprint "eagle-import:0603-CAP")
      (fields
        (field (name "CAPACITANCE") "0.1µF")
        (field (name "MANUFACTURER") "Vishay Vitramon")
        (field (name "MPN") "VJ0603Y104JXQPW1BC")
        (field (name "TOLERANCE") "5%")
        (field (name "VOLTAGE") "10V")
      )
      (libsource (lib "eagle-import") (part "CAPACITOR_?_060310V_0.1UF"))
    )
    (comp (ref "C26")
      (value "CAPACITOR_0603_50V_0.1UF")
      (footprint "eagle-import:0603-CAP")
      (fields
        (field (name "CAPACITANCE") "0.1µF")
        (field (name "MANUFACTURER") "Yageo")
        (field (name "MPN") "CC0603KRX7R9BB104")
        (field (name "TOLERANCE") "10%")
        (field (name "VOLTAGE") "50V")
      )
      (libsource (lib "eagle-import") (part "CAPACITOR_?_060350V_0.1UF"))
    )
    (comp (ref "C27")
      (value "CAPACITOR_0603_50V_1UF")
      (footprint "eagle-import:0603-CAP")
      (fields
        (field (name "CAPACITANCE") "1uF")
        (field (name "MANUFACTURER") "Taiyo Yuden")
        (field (name "MPN") "UMK107BJ105KA-T")
        (field (name "TOLERANCE") "10%")
        (field (name "VOLTAGE") "50V")
      )
      (libsource (lib "eagle-import") (part "CAPACITOR_?_060350V_1UF"))
    )
    (comp (ref "D3")
      (value "LED_0603_BLUE")
      (footprint "eagle-import:0603-LED")
      (fields
        (field (name "COLOR") "Blue")
        (field (name "MANUFACTURER") "Kingbright")
        (field (name "MPN") "APT1608VBC/D")
      )
      (libsource (lib "eagle-import") (part "LED_?_0603BLUE"))
    )
    (comp (ref "D4")
      (value "LED_0603_BLUE")
      (footprint "eagle-import:0603-LED")
      (fields
        (field (name "COLOR") "Blue")
        (field (name "MANUFACTURER") "Kingbright")
        (field (name "MPN") "APT1608VBC/D")
      )
      (libsource (lib "eagle-import") (part "LED_?_0603BLUE"))
    )
    (comp (ref "D5")
      (value "LED_0603_ORANGE")
      (footprint "eagle-import:0603-LED")
      (fields
        (field (name "COLOR") "Orange")
        (field (name "MANUFACTURER") "Kingbright")
        (field (name "MPN") "APT1608SECK")
      )
      (libsource (lib "eagle-import") (part "LED_?_0603ORANGE"))
    )
    (comp (ref "D6")
      (value "LED_0603_GREEN")
      (footprint "eagle-import:0603-LED")
      (fields
        (field (name "COLOR") "Green")
        (field (name "MANUFACTURER") "Kingbright")
        (field (name "MPN") "APT1608ZGCK")
      )
      (libsource (lib "eagle-import") (part "LED_?_0603GREEN"))
    )
    (comp (ref "D7")
      (value "TVS__8V")
      (footprint "eagle-import:SOT-23")
      (fields
        (field (name "MANUFACTURER") "Vishay General Semiconductor - Diodes Division")
        (field (name "MPN") "GSOT08-E3-08")
        (field (name "VOLTAGE") "8V")
      )
      (libsource (lib "eagle-import") (part "TVS_?_8V"))
    )
    (comp (ref "D8")
      (value "LED_0603_YELLOW")
      (footprint "eagle-import:0603-LED")
      (fields
        (field (name "COLOR") "Yellow")
        (field (name "MANUFACTURER") "Kingbright")
        (field (name "MPN") "APT1608SYCK/J3-PRV")
      )
      (libsource (lib "eagle-import") (part "LED_?_0603YELLOW"))
    )
    (comp (ref "D100")
      (value "SCHOTTKY_SOD323_60V")
      (footprint "eagle-import:SOD-323")
      (fields
        (field (name "MANUFACTURER") "Panjit International Inc.")
        (field (name "MPN") "MBR1060HEWS_R1_00001")
        (field (name "VOLTAGE") "60V")
      )
      (libsource (lib "eagle-import") (part "SCHOTTKY_?_SOD32360V"))
    )
    (comp (ref "F1")
      (value "FUSE_HOLDER_122")
      (footprint "eagle-import:122")
      (fields (field (name "MPN") "01220088Z") (field (name "MANUFACTURER") "Littelfuse"))
      (libsource (lib "eagle-import") (part "FUSE_HOLDER_122"))
    )
    (comp (ref "F2")
      (value "FUSE_HOLDER_122")
      (footprint "eagle-import:122")
      (fields (field (name "MPN") "01220088Z") (field (name "MANUFACTURER") "Littelfuse"))
      (libsource (lib "eagle-import") (part "FUSE_HOLDER_122"))
    )
    (comp (ref "GND")
      (value "TEST_POINT")
      (footprint "eagle-import:5015")
      (fields (field (name "MPN") "5015") (field (name "MANUFACTURER") "Keystone Electronics"))
      (libsource (lib "eagle-import") (part "TEST_POINT"))
    )
    (comp (ref "K1")
      (value "RELAY_SPST_NO_D_24")
      (footprint "eagle-import:D")
      (fields (field (name "MANUFACTURER") "Sensata-Cynergy3") (field (name "MPN") "DAR72410"))
      (libsource (lib "eagle-import") (part "RELAY_SPST_NO_?D_24"))
    )
    (comp (ref "PACK+")
      (value "TEST_POINT")
      (footprint "eagle-import:5015")
      (fields (field (name "MPN") "5015") (field (name "MANUFACTURER") "Keystone Electronics"))
      (libsource (lib "eagle-import") (part "TEST_POINT"))
    )
    (comp (ref "PACK+FUSED")
      (value "TEST_POINT")
      (footprint "eagle-import:5015")
      (fields (field (name "MPN") "5015") (field (name "MANUFACTURER") "Keystone Electronics"))
      (libsource (lib "eagle-import") (part "TEST_POINT"))
    )
    (comp (ref "PRECHARGE_OK")
      (value "TEST_POINT")
      (footprint "eagle-import:5015")
      (fields (field (name "MPN") "5015") (field (name "MANUFACTURER") "Keystone Electronics"))
      (libsource (lib "eagle-import") (part "TEST_POINT"))
    )
    (comp (ref "Q2")
      (value "TRANSISTOR_N_MOS__PMV15ENEA")
      (footprint "eagle-import:SOT-23")
      (fields (field (name "MANUFACTURER") "Nexperia USA Inc.") (field (name "MPN") "PMV15ENEAR"))
      (libsource (lib "eagle-import") (part "TRANSISTOR_N_MOS_?_PMV15ENEA"))
    )
    (comp (ref "R13")
      (value "RESISTOR_B20-SHORTENED_1.5K")
      (footprint "eagle-import:B20-SHORTENED")
      (fields
        (field (name "MANUFACTURER") "Ohmite")
        (field (name "MPN") "B20J1K5E")
        (field (name "POWER") "20W")
        (field (name "RESISTANCE") "1.5K")
      )
      (libsource (lib "eagle-import") (part "RESISTOR_?_B20-SHORTENED1.5K"))
    )
    (comp (ref "R23")
      (value "RESISTOR_B20-SHORTENED_1.5K")
      (footprint "eagle-import:B20-SHORTENED")
      (fields
        (field (name "MANUFACTURER") "Ohmite")
        (field (name "MPN") "B20J1K5E")
        (field (name "POWER") "20W")
        (field (name "RESISTANCE") "1.5K")
      )
      (libsource (lib "eagle-import") (part "RESISTOR_?_B20-SHORTENED1.5K"))
    )
    (comp (ref "R24")
      (value "RESISTOR_0603_39")
      (footprint "eagle-import:0603-RES")
      (fields
        (field (name "MANUFACTURER") "Yageo")
        (field (name "MPN") "RT0603BRD0739RL")
        (field (name "POWER") "0.1W")
        (field (name "RESISTANCE") "39")
      )
      (libsource (lib "eagle-import") (part "RESISTOR_?_060339"))
    )
    (comp (ref "R25")
      (value "RESISTOR_0603_2K")
      (footprint "eagle-import:0603-RES")
      (fields
        (field (name "MANUFACTURER") "Panasonic Electronic Components")
        (field (name "MPN") "ERJ-UP3F2001V")
        (field (name "POWER") "0.25W")
        (field (name "RESISTANCE") "2k")
      )
      (libsource (lib "eagle-import") (part "RESISTOR_?_06032K"))
    )
    (comp (ref "R26")
      (value "RESISTOR_0603_1K")
      (footprint "eagle-import:0603-RES")
      (fields
        (field (name "MANUFACTURER") "TE Connectivity Passive Product")
        (field (name "MPN") " CPF-A-0603B1K0E")
        (field (name "POWER") "0.0625W")
        (field (name "RESISTANCE") "1k")
      )
      (libsource (lib "eagle-import") (part "RESISTOR_?_06031K"))
    )
    (comp (ref "R27")
      (value "RESISTOR_0603_2K")
      (footprint "eagle-import:0603-RES")
      (fields
        (field (name "MANUFACTURER") "Panasonic Electronic Components")
        (field (name "MPN") "ERJ-UP3F2001V")
        (field (name "POWER") "0.25W")
        (field (name "RESISTANCE") "2k")
      )
      (libsource (lib "eagle-import") (part "RESISTOR_?_06032K"))
    )
    (comp (ref "R28")
      (value "RESISTOR_0603_10K")
      (footprint "eagle-import:0603-RES")
      (fields
        (field (name "MANUFACTURER") "Panasonic Electronic Components")
        (field (name "MPN") "ERA-3ARB103V")
        (field (name "POWER") "0.1W")
        (field (name "RESISTANCE") "10k")
      )
      (libsource (lib "eagle-import") (part "RESISTOR_?_060310K"))
    )
    (comp (ref "R29")
      (value "RESISTOR_0603_1K")
      (footprint "eagle-import:0603-RES")
      (fields
        (field (name "MANUFACTURER") "TE Connectivity Passive Product")
        (field (name "MPN") " CPF-A-0603B1K0E")
        (field (name "POWER") "0.0625W")
        (field (name "RESISTANCE") "1k")
      )
      (libsource (lib "eagle-import") (part "RESISTOR_?_06031K"))
    )
    (comp (ref "R30")
      (value "RESISTOR_0603_3.3K")
      (footprint "eagle-import:0603-RES")
      (fields
        (field (name "MANUFACTURER") "Panasonic Electronic Components")
        (field (name "MPN") "ERJ-PB3D3301V")
        (field (name "POWER") "0.3W")
        (field (name "RESISTANCE") "3.3k")
      )
      (libsource (lib "eagle-import") (part "RESISTOR_?_06033.3K"))
    )
    (comp (ref "R31")
      (value "RESISTOR_0603_1K")
      (footprint "eagle-import:0603-RES")
      (fields
        (field (name "MANUFACTURER") "TE Connectivity Passive Product")
        (field (name "MPN") " CPF-A-0603B1K0E")
        (field (name "POWER") "0.0625W")
        (field (name "RESISTANCE") "1k")
      )
      (libsource (lib "eagle-import") (part "RESISTOR_?_06031K"))
    )
    (comp (ref "R32")
      (value "RESISTOR_0603_75K")
      (footprint "eagle-import:0603-RES")
      (fields
        (field (name "MANUFACTURER") "Yageo")
        (field (name "MPN") "RT0603BRE0775KL")
        (field (name "POWER") "0.1W")
        (field (name "RESISTANCE") "75k")
      )
      (libsource (lib "eagle-import") (part "RESISTOR_?_060375K"))
    )
    (comp (ref "R33")
      (value "RESISTOR_0603_10")
      (footprint "eagle-import:0603-RES")
      (fields
        (field (name "MANUFACTURER") "Yageo")
        (field (name "MPN") "RC0603FR-0710RL")
        (field (name "POWER") "0.1W")
        (field (name "RESISTANCE") "10")
      )
      (libsource (lib "eagle-import") (part "RESISTOR_?_060310"))
    )
    (comp (ref "R34")
      (value "RESISTOR_0805_1M")
      (footprint "eagle-import:0805-RES")
      (fields
        (field (name "MANUFACTURER") "Panasonic Electronic Components")
        (field (name "MPN") "ERJ-PB6B1004V")
        (field (name "POWER") "0.25W")
        (field (name "RESISTANCE") "1M")
      )
      (libsource (lib "eagle-import") (part "RESISTOR_?_08051M"))
    )
    (comp (ref "R35")
      (value "RESISTOR_0805_523K")
      (footprint "eagle-import:0805-RES")
      (fields
        (field (name "MANUFACTURER") "Panasonic Electronic Components")
        (field (name "MPN") "ERJ-PB6B5233V")
        (field (name "POWER") "0.25W")
        (field (name "RESISTANCE") "523k")
      )
      (libsource (lib "eagle-import") (part "RESISTOR_?_0805523K"))
    )
    (comp (ref "R42")
      (value "RESISTOR_0603_DNP")
      (footprint "eagle-import:0603-RES")
      (fields (field (name "RESISTANCE") "DNP"))
      (libsource (lib "eagle-import") (part "RESISTOR_?_0603DNP"))
    )
    (comp (ref "SHDN")
      (value "TEST_POINT")
      (footprint "eagle-import:5015")
      (fields (field (name "MPN") "5015") (field (name "MANUFACTURER") "Keystone Electronics"))
      (libsource (lib "eagle-import") (part "TEST_POINT"))
    )
    (comp (ref "TS+")
      (value "CONNECTOR-5_MICRO_V7S_")
      (footprint "eagle-import:MOLEX_MICROFIT_PTH_VERTICAL_07_SINGLE_SPACED")
      (fields (field (name "MPN") "43650-0717") (field (name "MANUFACTURER") "Molex"))
      (libsource (lib "eagle-import") (part "CONNECTOR-5_?_MICRO_V7S"))
    )
    (comp (ref "TS-")
      (value "CONNECTOR-5_MICRO_V6S_")
      (footprint "eagle-import:MOLEX_MICROFIT_PTH_VERTICAL_06_SINGLE_SPACED")
      (fields (field (name "MPN") "43650-0617") (field (name "MANUFACTURER") "Molex"))
      (libsource (lib "eagle-import") (part "CONNECTOR-5_?_MICRO_V6S"))
    )
    (comp (ref "TS-UNFUSED")
      (value "TEST_POINT")
      (footprint "eagle-import:5015")
      (fields (field (name "MPN") "5015") (field (name "MANUFACTURER") "Keystone Electronics"))
      (libsource (lib "eagle-import") (part "TEST_POINT"))
    )
    (comp (ref "U5")
      (value "RELAY_SOLIDSTATE_NO_AB38S-Q-AIRGAP")
      (footprint "eagle-import:SOP-04-AIRGAP")
      (fields
        (field (name "MPN") "AB38S-Q")
        (field (name "MANUFACTURER") "Comus International")
        (field (name "VOLTAGE") "600V")
      )
      (libsource (lib "eagle-import") (part "RELAY_SOLIDSTATE_NO_AB38S-Q-AIRGAP"))
    )
    (comp (ref "U10")
      (value "LTC6994-2")
      (footprint "eagle-import:SOT-23-6")
      (fields (field (name "MANUFACTURER") "Analog Devices Inc") (field (name "MPN") "LTC6994HS6-2#TRMPBF"))
      (libsource (lib "eagle-import") (part "LTC6994-2"))
    )
  )
  (nets
    (net (code "1") (name "+5V") (class "Default")
      (node (ref "+5V") (pin "1") (pinfunction "1_1") (pintype "passive"))
      (node (ref "A1") (pin "3") (pinfunction "OUT_3") (pintype "power_in"))
      (node (ref "C23") (pin "1") (pinfunction "1_1") (pintype "passive"))
      (node (ref "C24") (pin "1") (pinfunction "1_1") (pintype "passive"))
      (node (ref "C25") (pin "1") (pinfunction "1_1") (pintype "passive"))
      (node (ref "C31") (pin "1") (pinfunction "1_1") (pintype "passive"))
      (node (ref "C36") (pin "1") (pinfunction "1_1") (pintype "passive"))
      (node (ref "C44") (pin "1") (pinfunction "1_1") (pintype "passive"))
      (node (ref "C45") (pin "1") (pinfunction "1_1") (pintype "passive"))
      (node (ref "R26") (pin "1") (pinfunction "1_1") (pintype "passive"))
      (node (ref "R35") (pin "2") (pinfunction "2_2") (pintype "passive"))
      (node (ref "U10") (pin "5") (pinfunction "V+_5") (pintype "power_in"))
      (node (ref "U7") (pin "12") (pinfunction "VDD_12") (pintype "power_in"))
      (node (ref "U8") (pin "12") (pinfunction "VDD_12") (pintype "power_in"))
    )
    (net (code "2") (name "+24V") (class "Default")
      (node (ref "+24V") (pin "1") (pinfunction "1_1") (pintype "passive"))
      (node (ref "A1") (pin "1") (pinfunction "IN_1") (pintype "power_in"))
      (node (ref "ACU") (pin "1") (pinfunction "1_1") (pintype "passive"))
      (node (ref "C26") (pin "1") (pinfunction "1_1") (pintype "passive"))
      (node (ref "C27") (pin "1") (pinfunction "1_1") (pintype "passive"))
      (node (ref "R25") (pin "2") (pinfunction "2_2") (pintype "passive"))
    )
    (net (code "3") (name "AIL+") (class "Default")
      (node (ref "R20") (pin "1") (pinfunction "1_1") (pintype "passive"))
      (node (ref "TS-") (pin "3") (pinfunction "3_3") (pintype "passive"))
    )
    (net (code "4") (name "DCDC_ENABLE") (class "Default")
      (node (ref "D7") (pin "3") (pinfunction "C_3") (pintype "passive"))
      (node (ref "R28") (pin "2") (pinfunction "2_2") (pintype "passive"))
      (node (ref "R31") (pin "2") (pinfunction "2_2") (pintype "passive"))
      (node (ref "R33") (pin "1") (pinfunction "1_1") (pintype "passive"))
      (node (ref "U10") (pin "4") (pinfunction "OUT_4") (pintype "bidirectional"))
    )
    (net (code "5") (name "EN{slash}UVLO") (class "Default")
      (node (ref "EN/UVLO") (pin "1") (pinfunction "1_1") (pintype "passive"))
      (node (ref "R1") (pin "2") (pinfunction "2_2") (pintype "passive"))
      (node (ref "R41") (pin "1") (pinfunction "1_1") (pintype "passive"))
      (node (ref "R47") (pin "2") (pinfunction "2_2") (pintype "passive"))
      (node (ref "R48") (pin "2") (pinfunction "2_2") (pintype "passive"))
      (node (ref "U6") (pin "17") (pinfunction "EN/UVLO_17") (pintype "input"))
    )
    (net (code "6") (name "GND") (class "Default")
      (node (ref "A1") (pin "2") (pinfunction "GND_2") (pintype "power_in"))
      (node (ref "ACU") (pin "4") (pinfunction "4_4") (pintype "passive"))
      (node (ref "C23") (pin "2") (pinfunction "2_2") (pintype "passive"))
      (node (ref "C24") (pin "2") (pinfunction "2_2") (pintype "passive"))
      (node (ref "C25") (pin "2") (pinfunction "2_2") (pintype "passive"))
      (node (ref "C26") (pin "2") (pinfunction "2_2") (pintype "passive"))
      (node (ref "C27") (pin "2") (pinfunction "2_2") (pintype "passive"))
      (node (ref "C31") (pin "2") (pinfunction "2_2") (pintype "passive"))
      (node (ref "C36") (pin "2") (pinfunction "2_2") (pintype "passive"))
      (node (ref "C37") (pin "2") (pinfunction "2_2") (pintype "passive"))
      (node (ref "C44") (pin "2") (pinfunction "2_2") (pintype "passive"))
      (node (ref "C45") (pin "2") (pinfunction "2_2") (pintype "passive"))
      (node (ref "C46") (pin "2") (pinfunction "2_2") (pintype "passive"))
      (node (ref "D3") (pin "1") (pinfunction "C_1") (pintype "passive"))
      (node (ref "D4") (pin "1") (pinfunction "C_1") (pintype "passive"))
      (node (ref "D5") (pin "1") (pinfunction "C_1") (pintype "passive"))
      (node (ref "D6") (pin "1") (pinfunction "C_1") (pintype "passive"))
      (node (ref "D7") (pin "1") (pinfunction "A_1") (pintype "passive"))
      (node (ref "D8") (pin "1") (pinfunction "C_1") (pintype "passive"))
      (node (ref "GND") (pin "1") (pinfunction "1_1") (pintype "passive"))
      (node (ref "Q2") (pin "2") (pinfunction "S_2") (pintype "passive"))
      (node (ref "R28") (pin "1") (pinfunction "1_1") (pintype "passive"))
      (node (ref "R32") (pin "1") (pinfunction "1_1") (pintype "passive"))
      (node (ref "R34") (pin "1") (pinfunction "1_1") (pintype "passive"))
      (node (ref "U10") (pin "2") (pinfunction "GND_2") (pintype "power_in"))
      (node (ref "U5") (pin "2") (pinfunction "CONTROL-_2") (pintype "passive"))
      (node (ref "U7") (pin "15") (pinfunction "DCDC_GND_15") (pintype "power_in"))
      (node (ref "U7") (pin "9") (pinfunction "GND_9") (pintype "power_in"))
      (node (ref "U8") (pin "15") (pinfunction "DCDC_GND_15") (pintype "power_in"))
      (node (ref "U8") (pin "9") (pinfunction "GND_9") (pintype "power_in"))
    )
    (net (code "7") (name "INTVCC") (class "Default")
      (node (ref "C33") (pin "1") (pinfunction "1_1") (pintype "passive"))
      (node (ref "R1") (pin "1") (pinfunction "1_1") (pintype "passive"))
      (node (ref "U6") (pin "8") (pinfunction "INTVCC_8") (pintype "passive"))
    )
    (net (code "8") (name "IP+") (class "Default")
      (node (ref "ACU") (pin "5") (pinfunction "5_5") (pintype "passive"))
      (node (ref "IP+") (pin "1") (pinfunction "1_1") (pintype "passive"))
      (node (ref "U8") (pin "11") (pinfunction "OUTP_11") (pintype "bidirectional"))
    )
    (net (code "9") (name "IP-") (class "Default")
      (node (ref "ACU") (pin "6") (pinfunction "6_6") (pintype "passive"))
      (node (ref "IP-") (pin "1") (pinfunction "1_1") (pintype "passive"))
      (node (ref "U8") (pin "10") (pinfunction "OUTN_10") (pintype "output"))
    )
    (net (code "10") (name "IT+") (class "Default")
      (node (ref "ACU") (pin "7") (pinfunction "7_7") (pintype "passive"))
      (node (ref "IT+") (pin "1") (pinfunction "1_1") (pintype "passive"))
      (node (ref "U7") (pin "11") (pinfunction "OUTP_11") (pintype "bidirectional"))
    )
    (net (code "11") (name "IT-") (class "Default")
      (node (ref "ACU") (pin "8") (pinfunction "8_8") (pintype "passive"))
      (node (ref "IT-") (pin "1") (pinfunction "1_1") (pintype "passive"))
      (node (ref "U7") (pin "10") (pinfunction "OUTN_10") (pintype "output"))
    )
    (net (code "12") (name "Net-(C30-Pad1)") (class "Default")
      (node (ref "C30") (pin "1") (pinfunction "1_1") (pintype "passive"))
      (node (ref "R40") (pin "1") (pinfunction "1_1") (pintype "passive"))
    )
    (net (code "13") (name "Net-(C54-Pad1)") (class "Default")
      (node (ref "C54") (pin "1") (pinfunction "1_1") (pintype "passive"))
      (node (ref "R56") (pin "2") (pinfunction "2_2") (pintype "passive"))
    )
    (net (code "14") (name "Net-(C55-Pad1)") (class "Default")
      (node (ref "C55") (pin "1") (pinfunction "1_1") (pintype "passive"))
      (node (ref "D10") (pin "C") (pinfunction "C_C") (pintype "passive"))
      (node (ref "R45") (pin "2") (pinfunction "2_2") (pintype "passive"))
    )
    (net (code "15") (name "Net-(C56-Pad1)") (class "Default")
      (node (ref "C56") (pin "1") (pinfunction "1_1") (pintype "passive"))
      (node (ref "D2") (pin "A") (pinfunction "A_A") (pintype "passive"))
      (node (ref "D9") (pin "C") (pinfunction "C_C") (pintype "passive"))
      (node (ref "R15") (pin "2") (pinfunction "2_2") (pintype "passive"))
    )
    (net (code "16") (name "Net-(D3-A)") (class "Default")
      (node (ref "D3") (pin "2") (pinfunction "A_2") (pintype "passive"))
      (node (ref "R25") (pin "1") (pinfunction "1_1") (pintype "passive"))
    )
    (net (code "17") (name "Net-(D4-A)") (class "Default")
      (node (ref "D4") (pin "2") (pinfunction "A_2") (pintype "passive"))
      (node (ref "R26") (pin "2") (pinfunction "2_2") (pintype "passive"))
    )
    (net (code "18") (name "Net-(D5-A)") (class "Default")
      (node (ref "D5") (pin "2") (pinfunction "A_2") (pintype "passive"))
      (node (ref "R27") (pin "1") (pinfunction "1_1") (pintype "passive"))
    )
    (net (code "19") (name "Net-(D6-A)") (class "Default")
      (node (ref "D6") (pin "2") (pinfunction "A_2") (pintype "passive"))
      (node (ref "R29") (pin "1") (pinfunction "1_1") (pintype "passive"))
    )
    (net (code "20") (name "Net-(D8-A)") (class "Default")
      (node (ref "D8") (pin "2") (pinfunction "A_2") (pintype "passive"))
      (node (ref "R31") (pin "1") (pinfunction "1_1") (pintype "passive"))
    )
    (net (code "21") (name "Net-(K1-COIL-)") (class "Default")
      (node (ref "D100") (pin "A") (pinfunction "A_A") (pintype "passive"))
      (node (ref "K1") (pin "3") (pinfunction "COIL-_3") (pintype "bidirectional"))
      (node (ref "Q2") (pin "3") (pinfunction "D_3") (pintype "passive"))
    )
    (net (code "22") (name "Net-(K1-CONTACT2)") (class "Default")
      (node (ref "K1") (pin "1") (pinfunction "CONTACT2_1") (pintype "bidirectional"))
      (node (ref "R13") (pin "1") (pinfunction "1_1") (pintype "passive"))
      (node (ref "R23") (pin "1") (pinfunction "1_1") (pintype "passive"))
    )
    (net (code "23") (name "Net-(LED_+12V1-A)") (class "Default")
      (node (ref "LED_+12V1") (pin "2") (pinfunction "A_2") (pintype "passive"))
      (node (ref "R50") (pin "1") (pinfunction "1_1") (pintype "passive"))
    )
    (net (code "24") (name "Net-(Q2-G)") (class "Default")
      (node (ref "Q2") (pin "1") (pinfunction "G_1") (pintype "passive"))
      (node (ref "R33") (pin "2") (pinfunction "2_2") (pintype "passive"))
    )
    (net (code "25") (name "Net-(R41-Pad2)") (class "Default")
      (node (ref "R41") (pin "2") (pinfunction "2_2") (pintype "passive"))
      (node (ref "R46") (pin "1") (pinfunction "1_1") (pintype "passive"))
    )
    (net (code "26") (name "Net-(R45-Pad1)") (class "Default")
      (node (ref "R45") (pin "1") (pinfunction "1_1") (pintype "passive"))
      (node (ref "R46") (pin "2") (pinfunction "2_2") (pintype "passive"))
    )
    (net (code "27") (name "Net-(R52-Pad2)") (class "Default")
      (node (ref "R52") (pin "2") (pinfunction "2_2") (pintype "passive"))
      (node (ref "R53") (pin "1") (pinfunction "1_1") (pintype "passive"))
    )
    (net (code "28") (name "Net-(R53-Pad2)") (class "Default")
      (node (ref "R53") (pin "2") (pinfunction "2_2") (pintype "passive"))
      (node (ref "R54") (pin "1") (pinfunction "1_1") (pintype "passive"))
    )
    (net (code "29") (name "Net-(R56-Pad1)") (class "Default")
      (node (ref "R56") (pin "1") (pinfunction "1_1") (pintype "passive"))
      (node (ref "R61") (pin "2") (pinfunction "2_2") (pintype "passive"))
    )
    (net (code "30") (name "Net-(R57-Pad2)") (class "Default")
      (node (ref "R57") (pin "2") (pinfunction "2_2") (pintype "passive"))
      (node (ref "R58") (pin "1") (pinfunction "1_1") (pintype "passive"))
    )
    (net (code "31") (name "Net-(R58-Pad2)") (class "Default")
      (node (ref "R58") (pin "2") (pinfunction "2_2") (pintype "passive"))
      (node (ref "R59") (pin "1") (pinfunction "1_1") (pintype "passive"))
    )
    (net (code "32") (name "Net-(U5-CONTACT1)") (class "Default")
      (node (ref "R24") (pin "1") (pinfunction "1_1") (pintype "passive"))
      (node (ref "U5") (pin "3") (pinfunction "CONTACT1_3") (pintype "bidirectional"))
    )
    (net (code "33") (name "Net-(U5-CONTROL+)") (class "Default")
      (node (ref "R30") (pin "2") (pinfunction "2_2") (pintype "passive"))
      (node (ref "R42") (pin "2") (pinfunction "2_2") (pintype "passive"))
      (node (ref "U5") (pin "1") (pinfunction "CONTROL+_1") (pintype "passive"))
    )
    (net (code "34") (name "Net-(U6-BIAS)") (class "Default")
      (node (ref "C32") (pin "1") (pinfunction "1_1") (pintype "passive"))
      (node (ref "D2") (pin "C") (pinfunction "C_C") (pintype "passive"))
      (node (ref "U6") (pin "9") (pinfunction "BIAS_9") (pintype "input"))
    )
    (net (code "35") (name "Net-(U6-DCM)") (class "Default")
      (node (ref "C54") (pin "2") (pinfunction "2_2") (pintype "passive"))
      (node (ref "U6") (pin "10") (pinfunction "DCM_10") (pintype "input"))
    )
    (net (code "36") (name "Net-(U6-EP)") (class "Default")
      (node (ref "C30") (pin "2") (pinfunction "2_2") (pintype "passive"))
      (node (ref "C32") (pin "2") (pinfunction "2_2") (pintype "passive"))
      (node (ref "C33") (pin "2") (pinfunction "2_2") (pintype "passive"))
      (node (ref "C55") (pin "2") (pinfunction "2_2") (pintype "passive"))
      (node (ref "C56") (pin "2") (pinfunction "2_2") (pintype "passive"))
      (node (ref "D11") (pin "C") (pinfunction "C_C") (pintype "passive"))
      (node (ref "L1") (pin "2") (pinfunction "2_2") (pintype "passive"))
      (node (ref "R18") (pin "1") (pinfunction "1_1") (pintype "passive"))
      (node (ref "R47") (pin "1") (pinfunction "1_1") (pintype "passive"))
      (node (ref "R48") (pin "1") (pinfunction "1_1") (pintype "passive"))
      (node (ref "R49") (pin "1") (pinfunction "1_1") (pintype "passive"))
      (node (ref "R51") (pin "1") (pinfunction "1_1") (pintype "passive"))
      (node (ref "U6") (pin "15") (pinfunction "GND_15") (pintype "power_in"))
      (node (ref "U6") (pin "16") (pinfunction "SMODE_16") (pintype "input"))
      (node (ref "U6") (pin "20") (pinfunction "GND_20") (pintype "power_in"))
      (node (ref "U6") (pin "THERMAL") (pinfunction "EP_THERMAL") (pintype "power_in"))
    )
    (net (code "37") (name "Net-(U6-FB)") (class "Default")
      (node (ref "R15") (pin "1") (pinfunction "1_1") (pintype "passive"))
      (node (ref "R18") (pin "2") (pinfunction "2_2") (pintype "passive"))
      (node (ref "U6") (pin "12") (pinfunction "FB_12") (pintype "input"))
    )
    (net (code "38") (name "Net-(U6-IREG{slash}SS)") (class "Default")
      (node (ref "R49") (pin "2") (pinfunction "2_2") (pintype "passive"))
      (node (ref "U6") (pin "14") (pinfunction "IREG/SS_14") (pintype "passive"))
    )
    (net (code "39") (name "Net-(U6-SOURCE)") (class "Default")
      (node (ref "R51") (pin "2") (pinfunction "2_2") (pintype "passive"))
      (node (ref "U6") (pin "18") (pinfunction "SOURCE_18") (pintype "output"))
    )
    (net (code "40") (name "Net-(U6-VC)") (class "Default")
      (node (ref "R40") (pin "2") (pinfunction "2_2") (pintype "passive"))
      (node (ref "U6") (pin "13") (pinfunction "VC_13") (pintype "passive"))
    )
    (net (code "41") (name "Net-(U7-DCDC_IN)") (class "Default")
      (node (ref "C37") (pin "1") (pinfunction "1_1") (pintype "passive"))
      (node (ref "U7") (pin "13") (pinfunction "LDO_OUT_13") (pintype "power_in"))
      (node (ref "U7") (pin "16") (pinfunction "DCDC_IN_16") (pintype "power_in"))
    )
    (net (code "42") (name "Net-(U7-DCDC_OUT)") (class "Default")
      (node (ref "C40") (pin "1") (pinfunction "1_1") (pintype "passive"))
      (node (ref "C41") (pin "1") (pinfunction "1_1") (pintype "passive"))
      (node (ref "C42") (pin "2") (pinfunction "2_2") (pintype "passive"))
      (node (ref "U7") (pin "1") (pinfunction "DCDC_OUT_1") (pintype "power_in"))
      (node (ref "U7") (pin "3") (pinfunction "HLDO_IN_3") (pintype "power_in"))
    )
    (net (code "43") (name "Net-(U8-DCDC_IN)") (class "Default")
      (node (ref "C46") (pin "1") (pinfunction "1_1") (pintype "passive"))
      (node (ref "U8") (pin "13") (pinfunction "LDO_OUT_13") (pintype "power_in"))
      (node (ref "U8") (pin "16") (pinfunction "DCDC_IN_16") (pintype "power_in"))
    )
    (net (code "44") (name "Net-(U8-DCDC_OUT)") (class "Default")
      (node (ref "C49") (pin "1") (pinfunction "1_1") (pintype "passive"))
      (node (ref "C50") (pin "1") (pinfunction "1_1") (pintype "passive"))
      (node (ref "C51") (pin "2") (pinfunction "2_2") (pintype "passive"))
      (node (ref "U8") (pin "1") (pinfunction "DCDC_OUT_1") (pintype "power_in"))
      (node (ref "U8") (pin "3") (pinfunction "HLDO_IN_3") (pintype "power_in"))
    )
    (net (code "45") (name "Net-(U10-DIV)") (class "Default")
      (node (ref "R34") (pin "2") (pinfunction "2_2") (pintype "passive"))
      (node (ref "R35") (pin "1") (pinfunction "1_1") (pintype "passive"))
      (node (ref "U10") (pin "6") (pinfunction "DIV_6") (pintype "bidirectional"))
    )
    (net (code "46") (name "Net-(U10-SET)") (class "Default")
      (node (ref "R32") (pin "2") (pinfunction "2_2") (pintype "passive"))
      (node (ref "U10") (pin "3") (pinfunction "SET_3") (pintype "bidirectional"))
    )
    (net (code "47") (name "PACK+") (class "Default")
      (node (ref "K1") (pin "2") (pinfunction "CONTACT1_2") (pintype "bidirectional"))
      (node (ref "PACK+") (pin "1") (pinfunction "1_1") (pintype "passive"))
      (node (ref "TS+") (pin "5") (pinfunction "5_5") (pintype "passive"))
      (node (ref "U5") (pin "4") (pinfunction "CONTACT2_4") (pintype "bidirectional"))
    )
    (net (code "48") (name "PACK+FUSED") (class "Default")
      (node (ref "PACK+FUSED") (pin "1") (pinfunction "1_1") (pintype "passive"))
      (node (ref "R24") (pin "2") (pinfunction "2_2") (pintype "passive"))
      (node (ref "R59") (pin "2") (pinfunction "2_2") (pintype "passive"))
    )
    (net (code "49") (name "PACK_HLDO_OUT") (class "Default")
      (node (ref "C47") (pin "1") (pinfunction "1_1") (pintype "passive"))
      (node (ref "C48") (pin "1") (pinfunction "1_1") (pintype "passive"))
      (node (ref "PACK_HLDO") (pin "1") (pinfunction "1_1") (pintype "passive"))
      (node (ref "U8") (pin "5") (pinfunction "HLDO_OUT_5") (pintype "power_in"))
    )
    (net (code "50") (name "PACK_INP") (class "Default")
      (node (ref "C52") (pin "1") (pinfunction "1_1") (pintype "passive"))
      (node (ref "PACK_INP") (pin "1") (pinfunction "1_1") (pintype "passive"))
      (node (ref "R57") (pin "1") (pinfunction "1_1") (pintype "passive"))
      (node (ref "R60") (pin "2") (pinfunction "2_2") (pintype "passive"))
      (node (ref "U8") (pin "6") (pinfunction "INP_6") (pintype "bidirectional"))
    )
    (net (code "51") (name "PACK_ISO_DIAG") (class "Default")
      (node (ref "PACK_ISO_DIAG") (pin "1") (pinfunction "1_1") (pintype "passive"))
      (node (ref "U8") (pin "14") (pinfunction "DIAG_14") (pintype "open_collector"))
    )
    (net (code "52") (name "PRECHARGE_OK") (class "Default")
      (node (ref "ACU") (pin "3") (pinfunction "3_3") (pintype "passive"))
      (node (ref "PRECHARGE_OK") (pin "1") (pinfunction "1_1") (pintype "passive"))
      (node (ref "R29") (pin "2") (pinfunction "2_2") (pintype "passive"))
      (node (ref "U10") (pin "1") (pinfunction "IN_1") (pintype "bidirectional"))
    )
    (net (code "53") (name "SHDN") (class "Default")
      (node (ref "ACU") (pin "2") (pinfunction "2_2") (pintype "passive"))
      (node (ref "D100") (pin "C") (pinfunction "C_C") (pintype "passive"))
      (node (ref "K1") (pin "4") (pinfunction "COIL+_4") (pintype "bidirectional"))
      (node (ref "R27") (pin "2") (pinfunction "2_2") (pintype "passive"))
      (node (ref "R30") (pin "1") (pinfunction "1_1") (pintype "passive"))
      (node (ref "R42") (pin "1") (pinfunction "1_1") (pintype "passive"))
      (node (ref "SHDN") (pin "1") (pinfunction "1_1") (pintype "passive"))
    )
    (net (code "54") (name "TS+12V") (class "Default")
      (node (ref "C3") (pin "1") (pinfunction "1_1") (pintype "passive"))
      (node (ref "D12") (pin "C") (pinfunction "C_C") (pintype "passive"))
      (node (ref "D9") (pin "A") (pinfunction "A_A") (pintype "passive"))
      (node (ref "L1") (pin "1") (pinfunction "1_1") (pintype "passive"))
      (node (ref "R20") (pin "2") (pinfunction "2_2") (pintype "passive"))
      (node (ref "R50") (pin "2") (pinfunction "2_2") (pintype "passive"))
      (node (ref "TS+12V") (pin "1") (pinfunction "1_1") (pintype "passive"))
    )
    (net (code "55") (name "TS+FUSED") (class "Default")
      (node (ref "C35") (pin "1") (pinfunction "1_1") (pintype "passive"))
      (node (ref "D10") (pin "A") (pinfunction "A_A") (pintype "passive"))
      (node (ref "F1") (pin "3") (pinfunction "2_3") (pintype "passive"))
      (node (ref "F1") (pin "4") (pinfunction "2_4") (pintype "passive"))
      (node (ref "R54") (pin "2") (pinfunction "2_2") (pintype "passive"))
      (node (ref "R61") (pin "1") (pinfunction "1_1") (pintype "passive"))
      (node (ref "TS+") (pin "4") (pinfunction "4_4") (pintype "passive"))
      (node (ref "U6") (pin "1") (pinfunction "DRAIN_1") (pintype "open_collector"))
      (node (ref "U6") (pin "2") (pinfunction "DRAIN_2") (pintype "open_collector"))
      (node (ref "U6") (pin "3") (pinfunction "DRAIN_3") (pintype "open_collector"))
    )
    (net (code "56") (name "TS+UNFUSED") (class "Default")
      (node (ref "F1") (pin "1") (pinfunction "1_1") (pintype "passive"))
      (node (ref "F1") (pin "2") (pinfunction "1_2") (pintype "passive"))
      (node (ref "R13") (pin "2") (pinfunction "2_2") (pintype "passive"))
      (node (ref "R23") (pin "2") (pinfunction "2_2") (pintype "passive"))
      (node (ref "TS+") (pin "1") (pinfunction "1_1") (pintype "passive"))
      (node (ref "TS+") (pin "2") (pinfunction "2_2") (pintype "passive"))
    )
    (net (code "57") (name "TS-FUSED") (class "Default")
      (node (ref "C3") (pin "2") (pinfunction "2_2") (pintype "passive"))
      (node (ref "C35") (pin "2") (pinfunction "2_2") (pintype "passive"))
      (node (ref "C38") (pin "2") (pinfunction "2_2") (pintype "passive"))
      (node (ref "C39") (pin "2") (pinfunction "2_2") (pintype "passive"))
      (node (ref "C40") (pin "2") (pinfunction "2_2") (pintype "passive"))
      (node (ref "C41") (pin "2") (pinfunction "2_2") (pintype "passive"))
      (node (ref "C42") (pin "1") (pinfunction "1_1") (pintype "passive"))
      (node (ref "C43") (pin "2") (pinfunction "2_2") (pintype "passive"))
      (node (ref "C47") (pin "2") (pinfunction "2_2") (pintype "passive"))
      (node (ref "C48") (pin "2") (pinfunction "2_2") (pintype "passive"))
      (node (ref "C49") (pin "2") (pinfunction "2_2") (pintype "passive"))
      (node (ref "C50") (pin "2") (pinfunction "2_2") (pintype "passive"))
      (node (ref "C51") (pin "1") (pinfunction "1_1") (pintype "passive"))
      (node (ref "C52") (pin "2") (pinfunction "2_2") (pintype "passive"))
      (node (ref "D11") (pin "A") (pinfunction "A_A") (pintype "passive"))
      (node (ref "D12") (pin "A") (pinfunction "A_A") (pintype "passive"))
      (node (ref "F2") (pin "3") (pinfunction "2_3") (pintype "passive"))
      (node (ref "F2") (pin "4") (pinfunction "2_4") (pintype "passive"))
      (node (ref "LED_+12V1") (pin "1") (pinfunction "C_1") (pintype "passive"))
      (node (ref "R55") (pin "1") (pinfunction "1_1") (pintype "passive"))
      (node (ref "R60") (pin "1") (pinfunction "1_1") (pintype "passive"))
      (node (ref "TS-") (pin "1") (pinfunction "1_1") (pintype "passive"))
      (node (ref "TS-") (pin "2") (pinfunction "2_2") (pintype "passive"))
      (node (ref "TS-FUSED") (pin "1") (pinfunction "1_1") (pintype "passive"))
      (node (ref "U7") (pin "2") (pinfunction "DCDC_HGND_2") (pintype "power_in"))
      (node (ref "U7") (pin "7") (pinfunction "INN_7") (pintype "input"))
      (node (ref "U7") (pin "8") (pinfunction "HGND_8") (pintype "power_in"))
      (node (ref "U8") (pin "2") (pinfunction "DCDC_HGND_2") (pintype "power_in"))
      (node (ref "U8") (pin "7") (pinfunction "INN_7") (pintype "input"))
      (node (ref "U8") (pin "8") (pinfunction "HGND_8") (pintype "power_in"))
    )
    (net (code "58") (name "TS-UNFUSED") (class "Default")
      (node (ref "F2") (pin "1") (pinfunction "1_1") (pintype "passive"))
      (node (ref "F2") (pin "2") (pinfunction "1_2") (pintype "passive"))
      (node (ref "TS-") (pin "5") (pinfunction "5_5") (pintype "passive"))
      (node (ref "TS-UNFUSED") (pin "1") (pinfunction "1_1") (pintype "passive"))
    )
    (net (code "59") (name "TS_HLDO_OUT") (class "Default")
      (node (ref "C38") (pin "1") (pinfunction "1_1") (pintype "passive"))
      (node (ref "C39") (pin "1") (pinfunction "1_1") (pintype "passive"))
      (node (ref "TS_HLDO") (pin "1") (pinfunction "1_1") (pintype "passive"))
      (node (ref "U7") (pin "5") (pinfunction "HLDO_OUT_5") (pintype "power_in"))
    )
    (net (code "60") (name "TS_INP") (class "Default")
      (node (ref "C43") (pin "1") (pinfunction "1_1") (pintype "passive"))
      (node (ref "R52") (pin "1") (pinfunction "1_1") (pintype "passive"))
      (node (ref "R55") (pin "2") (pinfunction "2_2") (pintype "passive"))
      (node (ref "TS_INP") (pin "1") (pinfunction "1_1") (pintype "passive"))
      (node (ref "U7") (pin "6") (pinfunction "INP_6") (pintype "bidirectional"))
    )
    (net (code "61") (name "TS_ISO_DIAG") (class "Default")
      (node (ref "TS_ISO_DIAG") (pin "1") (pinfunction "1_1") (pintype "passive"))
      (node (ref "U7") (pin "14") (pinfunction "DIAG_14") (pintype "open_collector"))
    )
    (net (code "62") (name "unconnected-(TS+-Pad3)") (class "Default")
      (node (ref "TS+") (pin "3") (pinfunction "3_3") (pintype "passive"))
    )
    (net (code "63") (name "unconnected-(TS--Pad4)") (class "Default")
      (node (ref "TS-") (pin "4") (pinfunction "4_4") (pintype "passive"))
    )
    (net (code "64") (name "unconnected-(U6-NC-Pad19)") (class "Default")
      (node (ref "U6") (pin "19") (pinfunction "NC_19") (pintype "no_connect"))
    )
    (net (code "65") (name "unconnected-(U6-TC-Pad11)") (class "Default")
      (node (ref "U6") (pin "11") (pinfunction "TC_11") (pintype "passive"))
    )
    (net (code "66") (name "unconnected-(U7-NC-Pad4)") (class "Default")
      (node (ref "U7") (pin "4") (pinfunction "NC_4") (pintype "no_connect"))
    )
    (net (code "67") (name "unconnected-(U8-NC-Pad4)") (class "Default")
      (node (ref "U8") (pin "4") (pinfunction "NC_4") (pintype "no_connect"))
    )
  )
)
